# CN-Cape005-via08.net
KiCad netlist of a schematic drawn in EAGLE
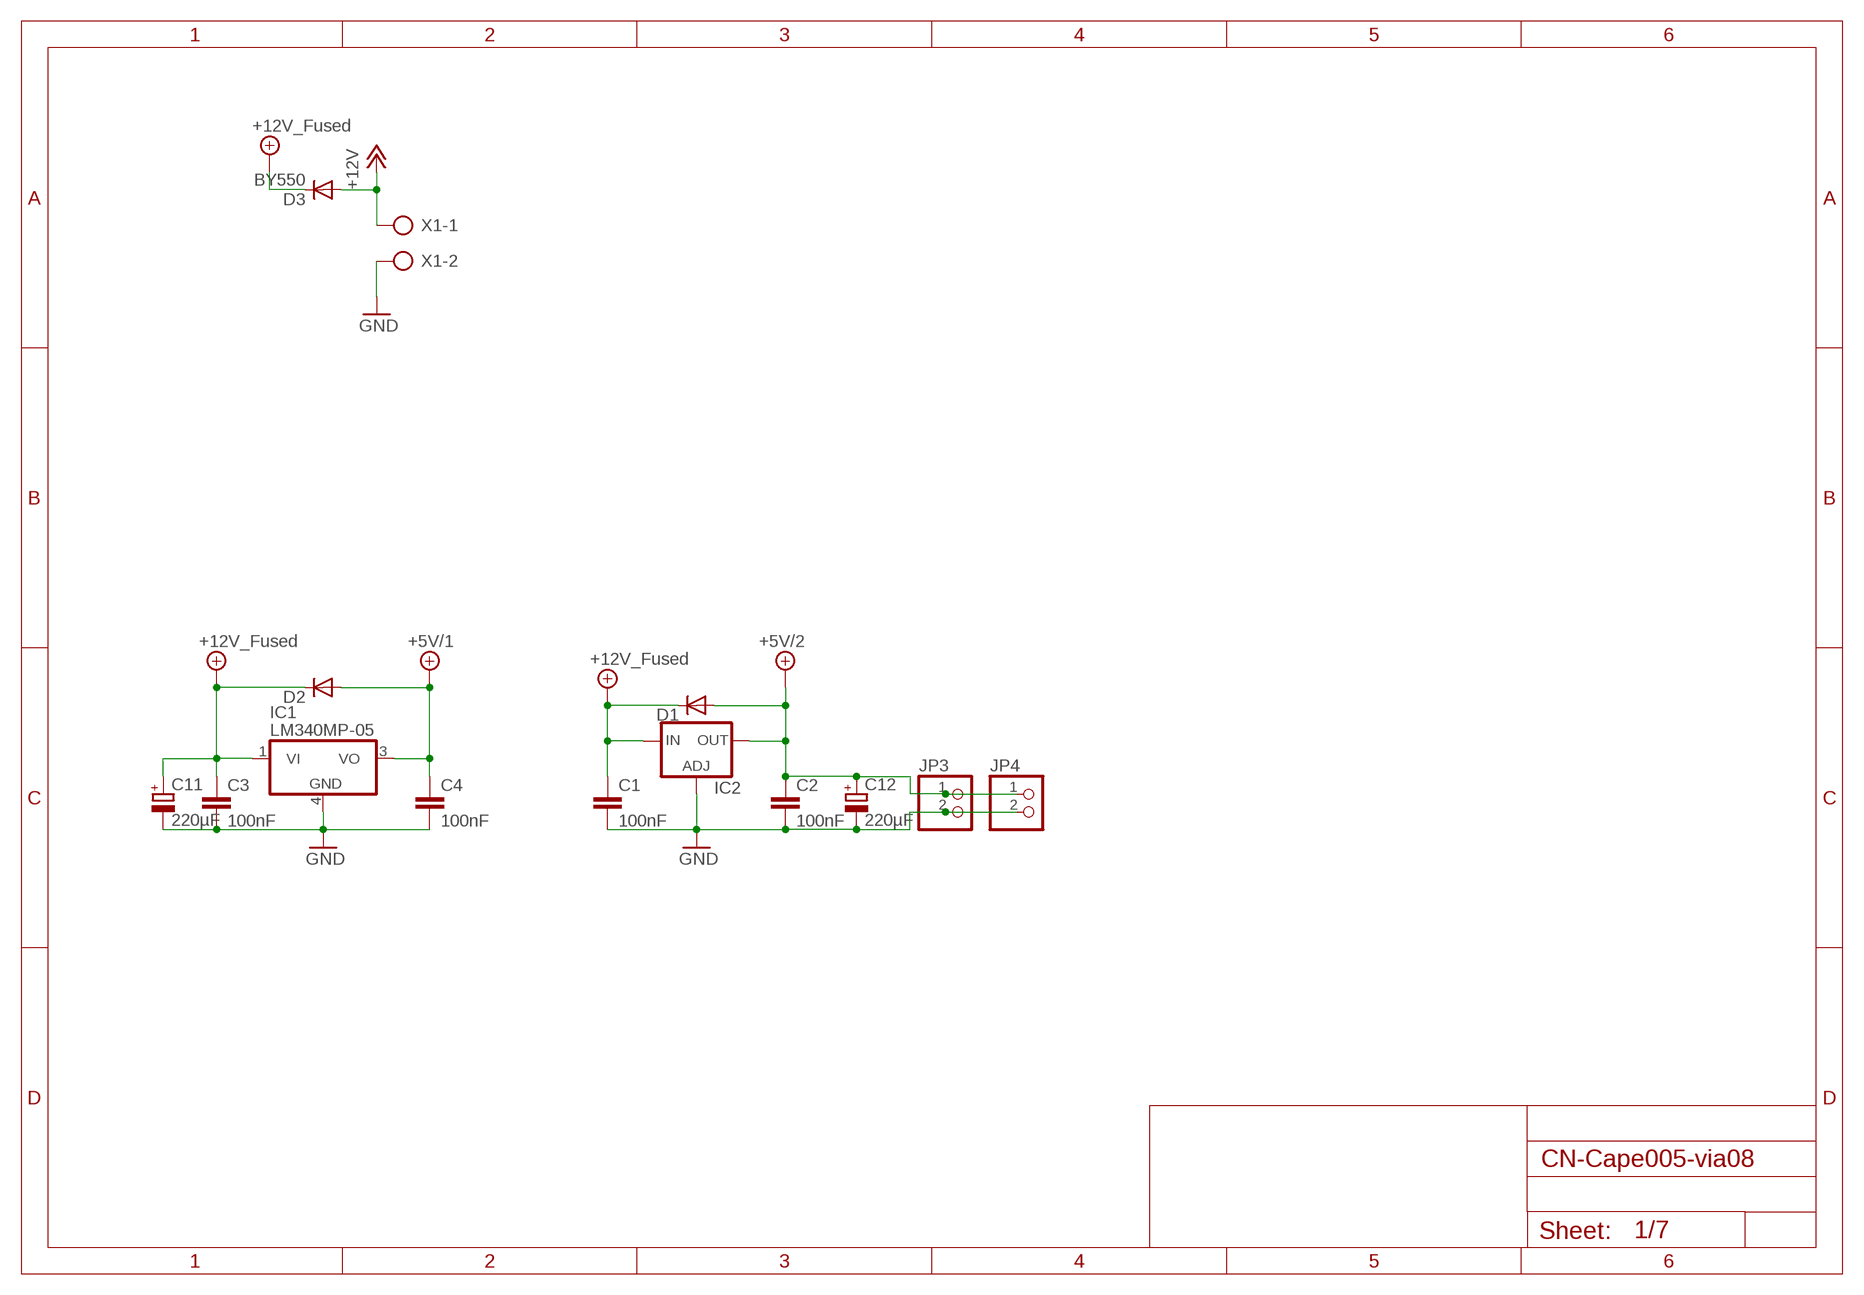
[diagram p0: schematic, sheet 1]
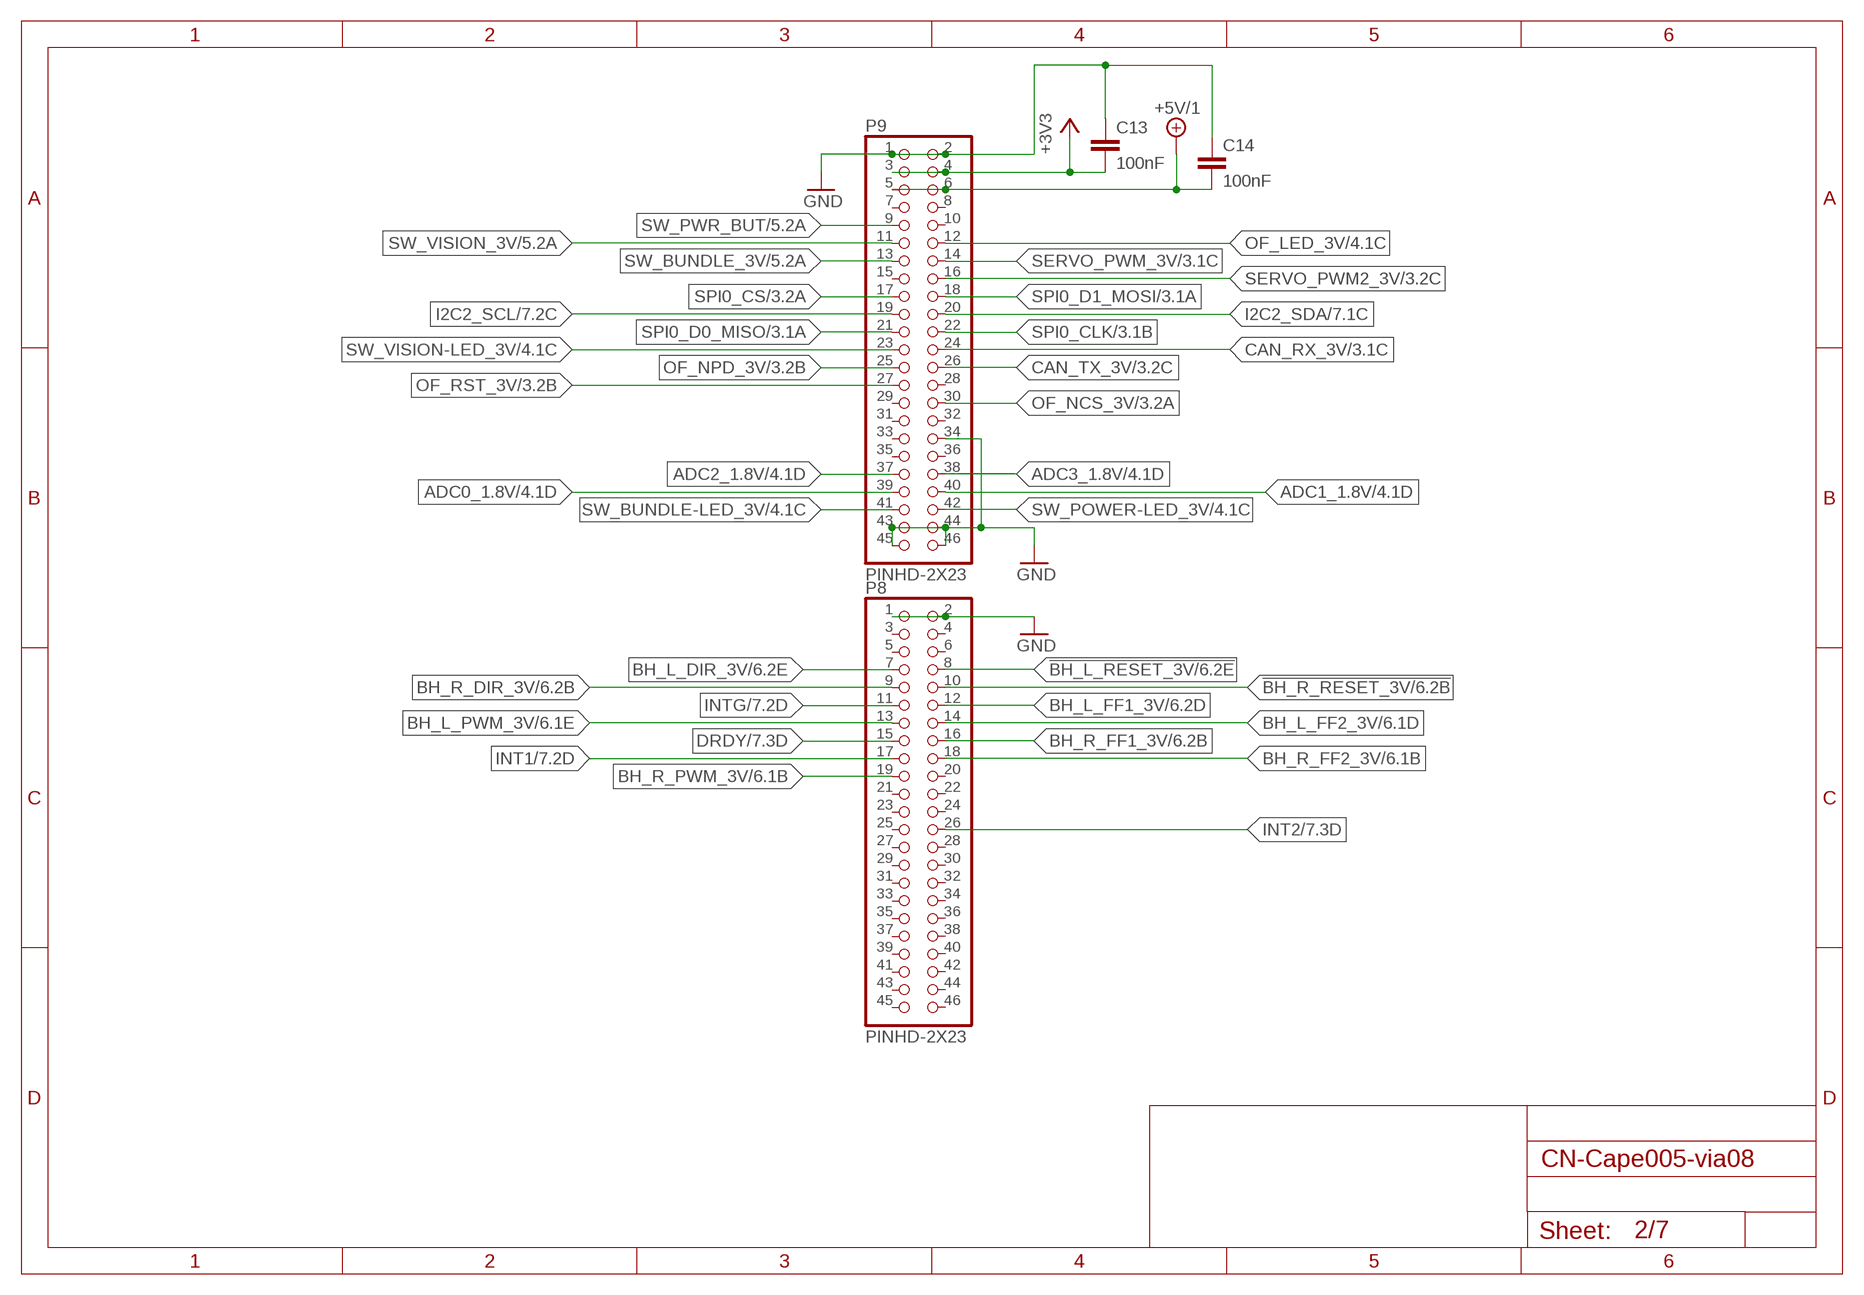
[diagram p1: schematic, sheet 2]
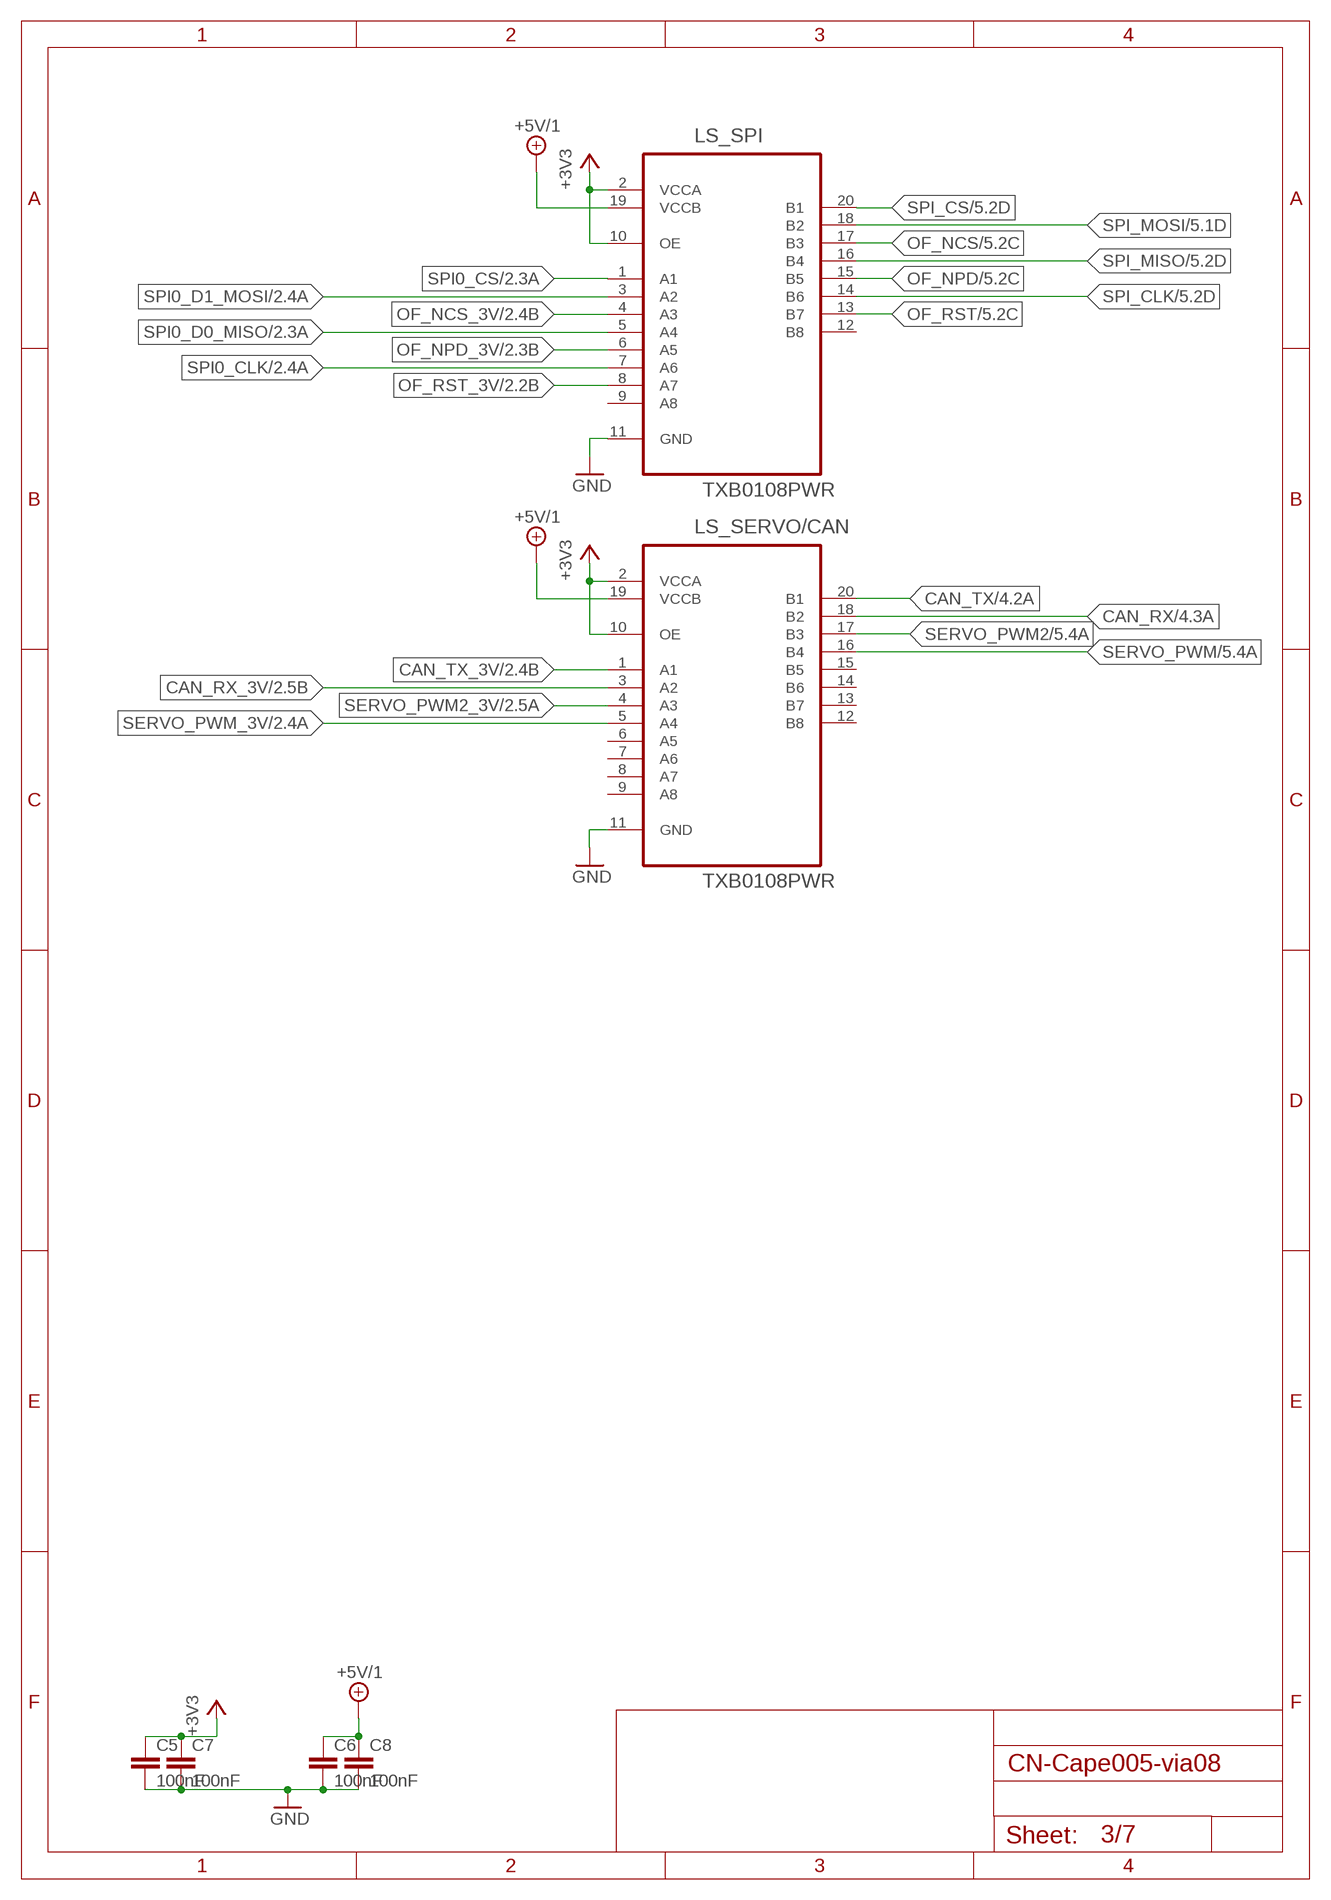
[diagram p2: schematic, sheet 3]
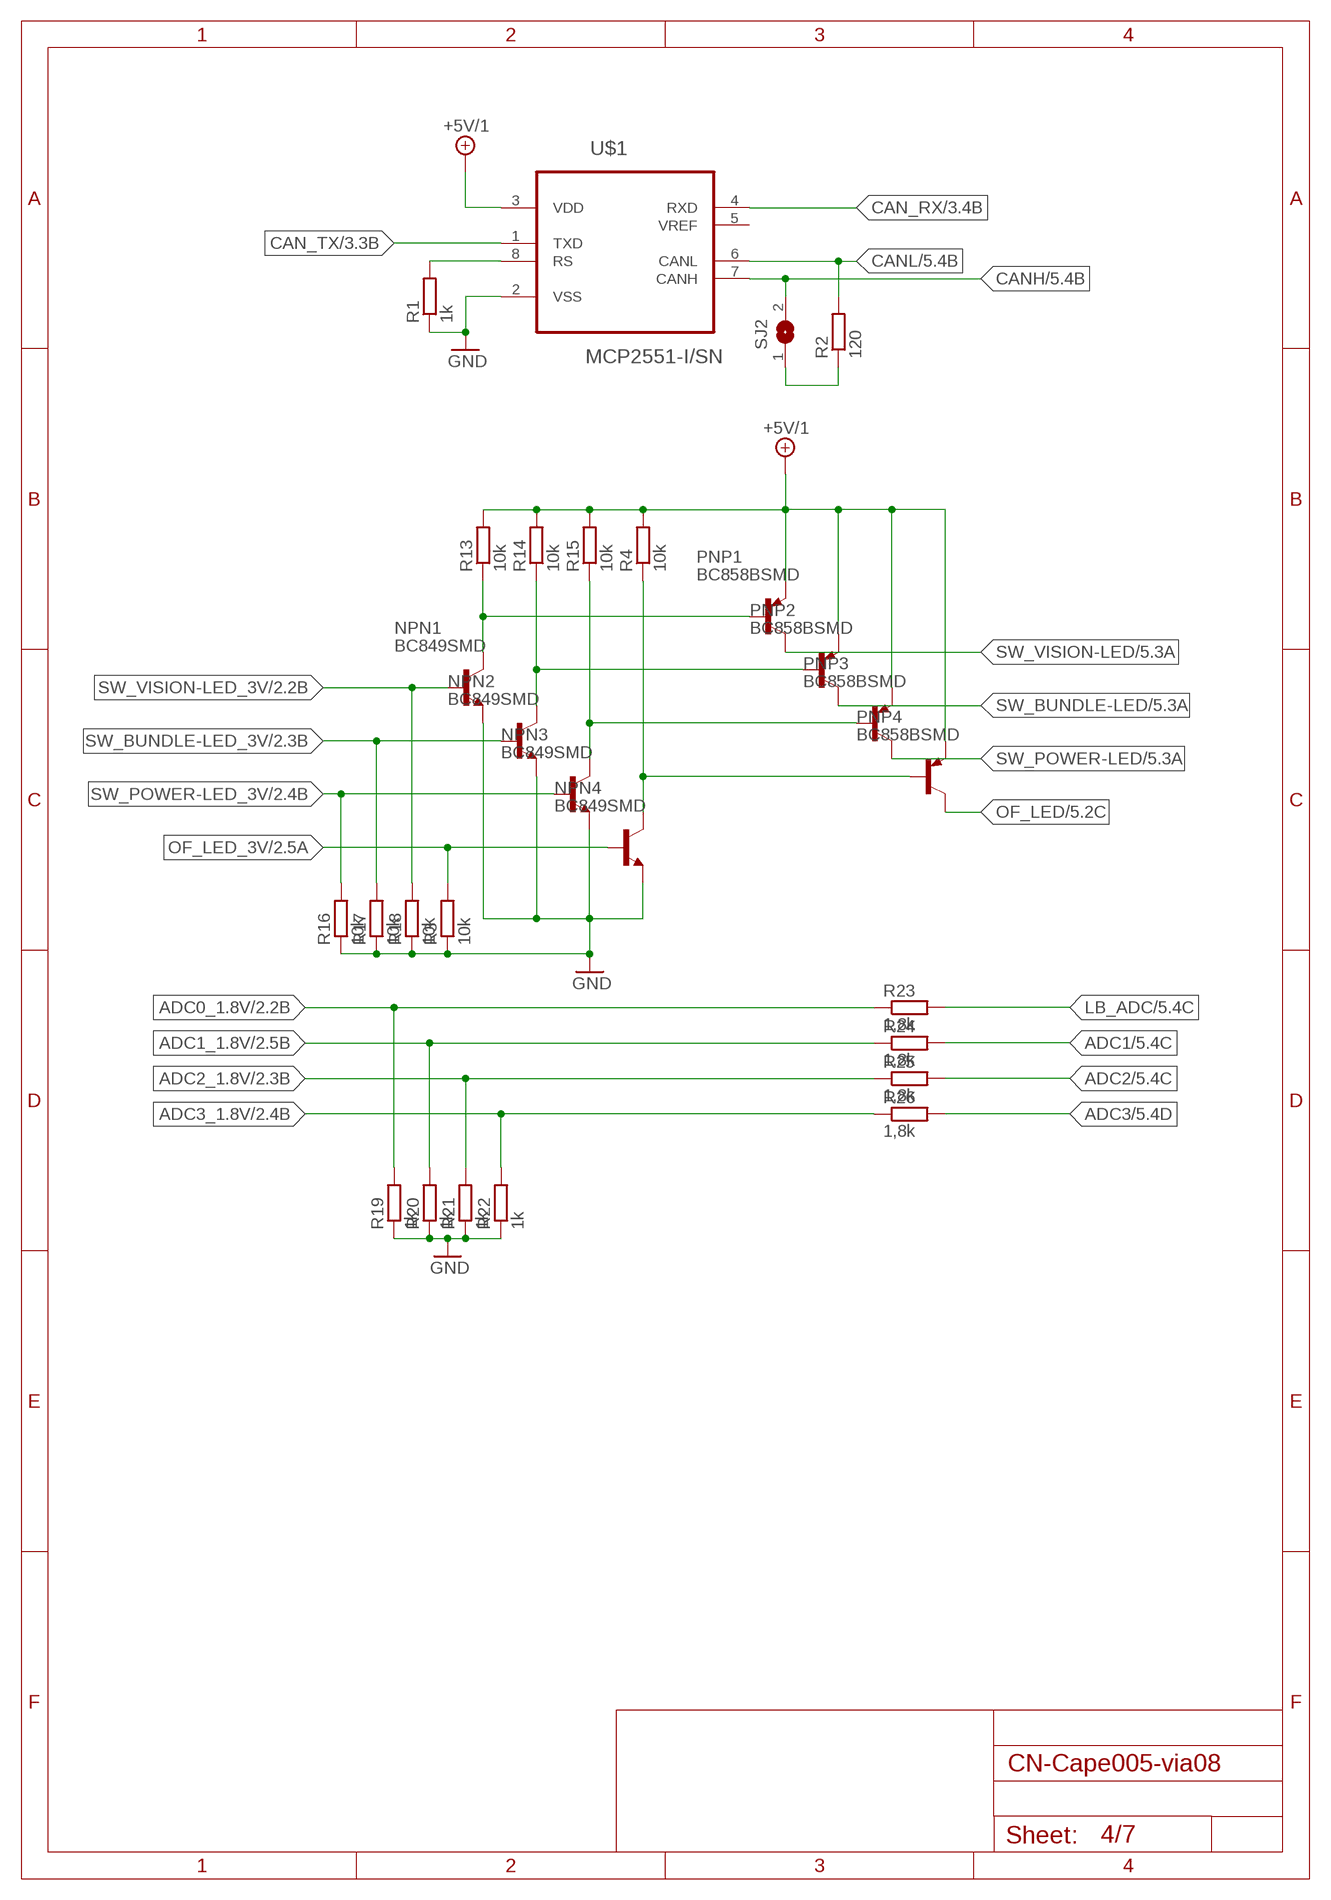
[diagram p3: schematic, sheet 4]
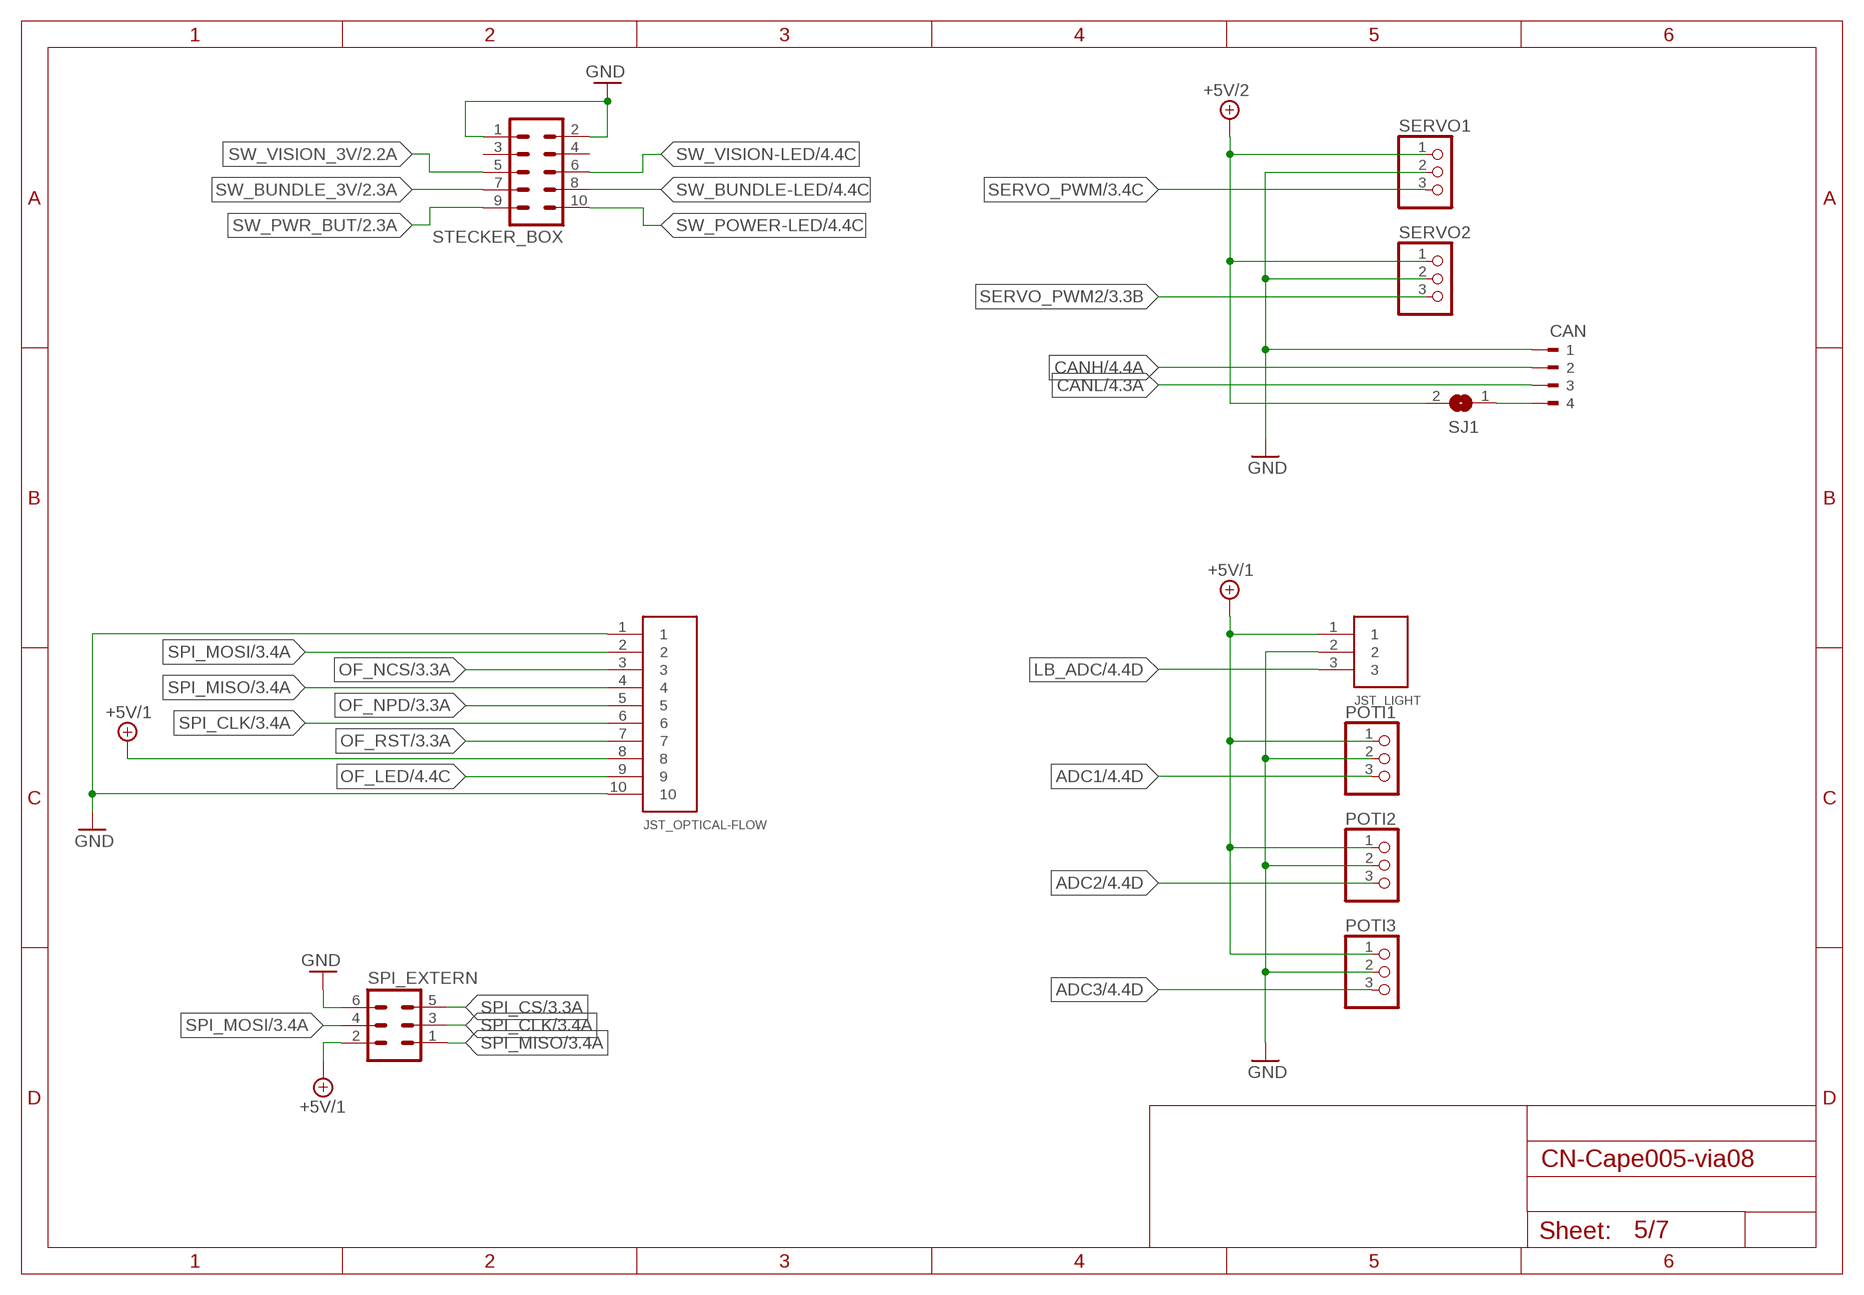
[diagram p4: schematic, sheet 5]
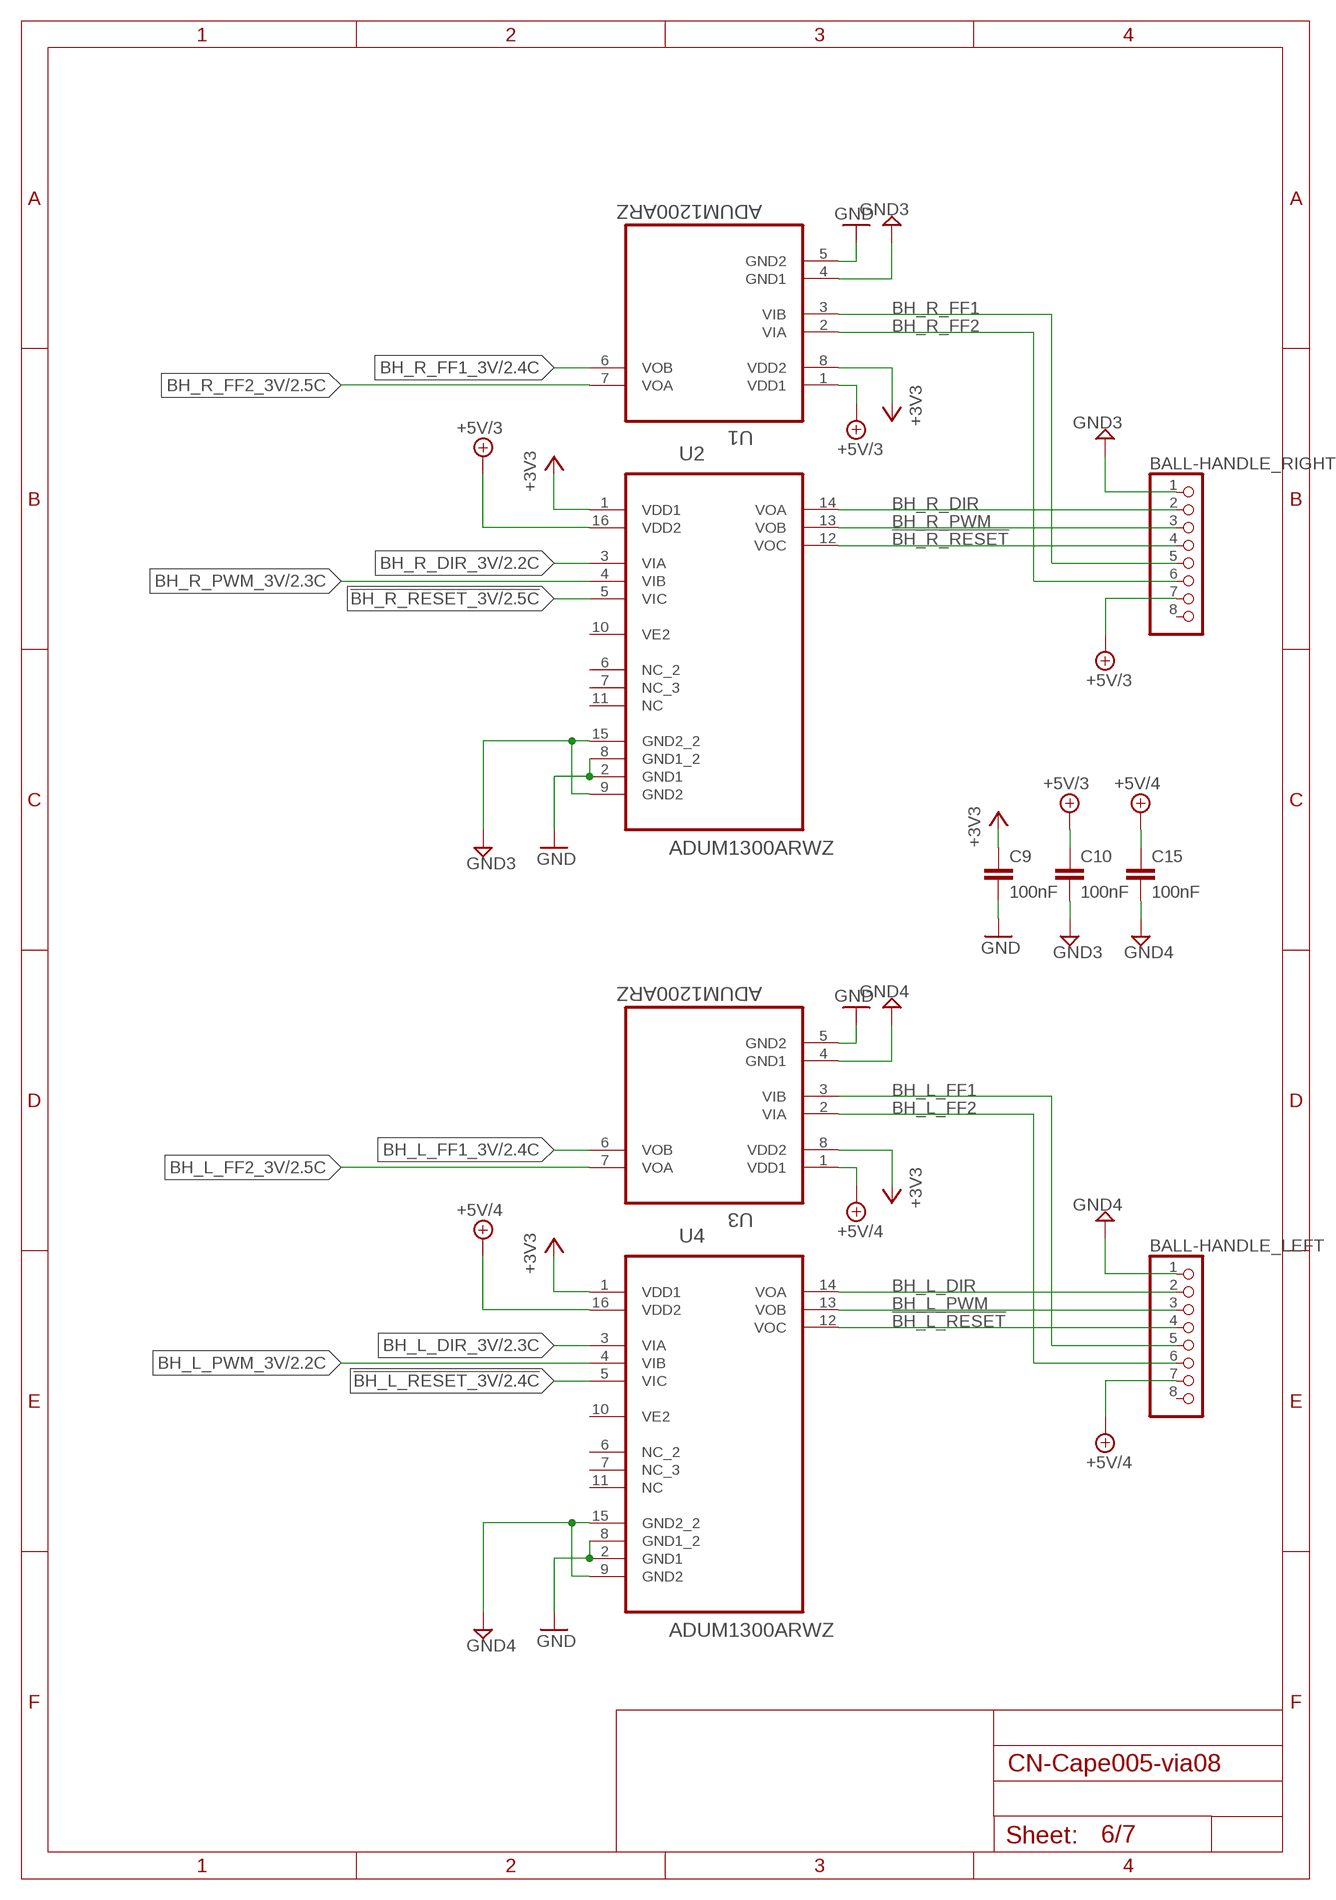
[diagram p5: schematic, sheet 6]
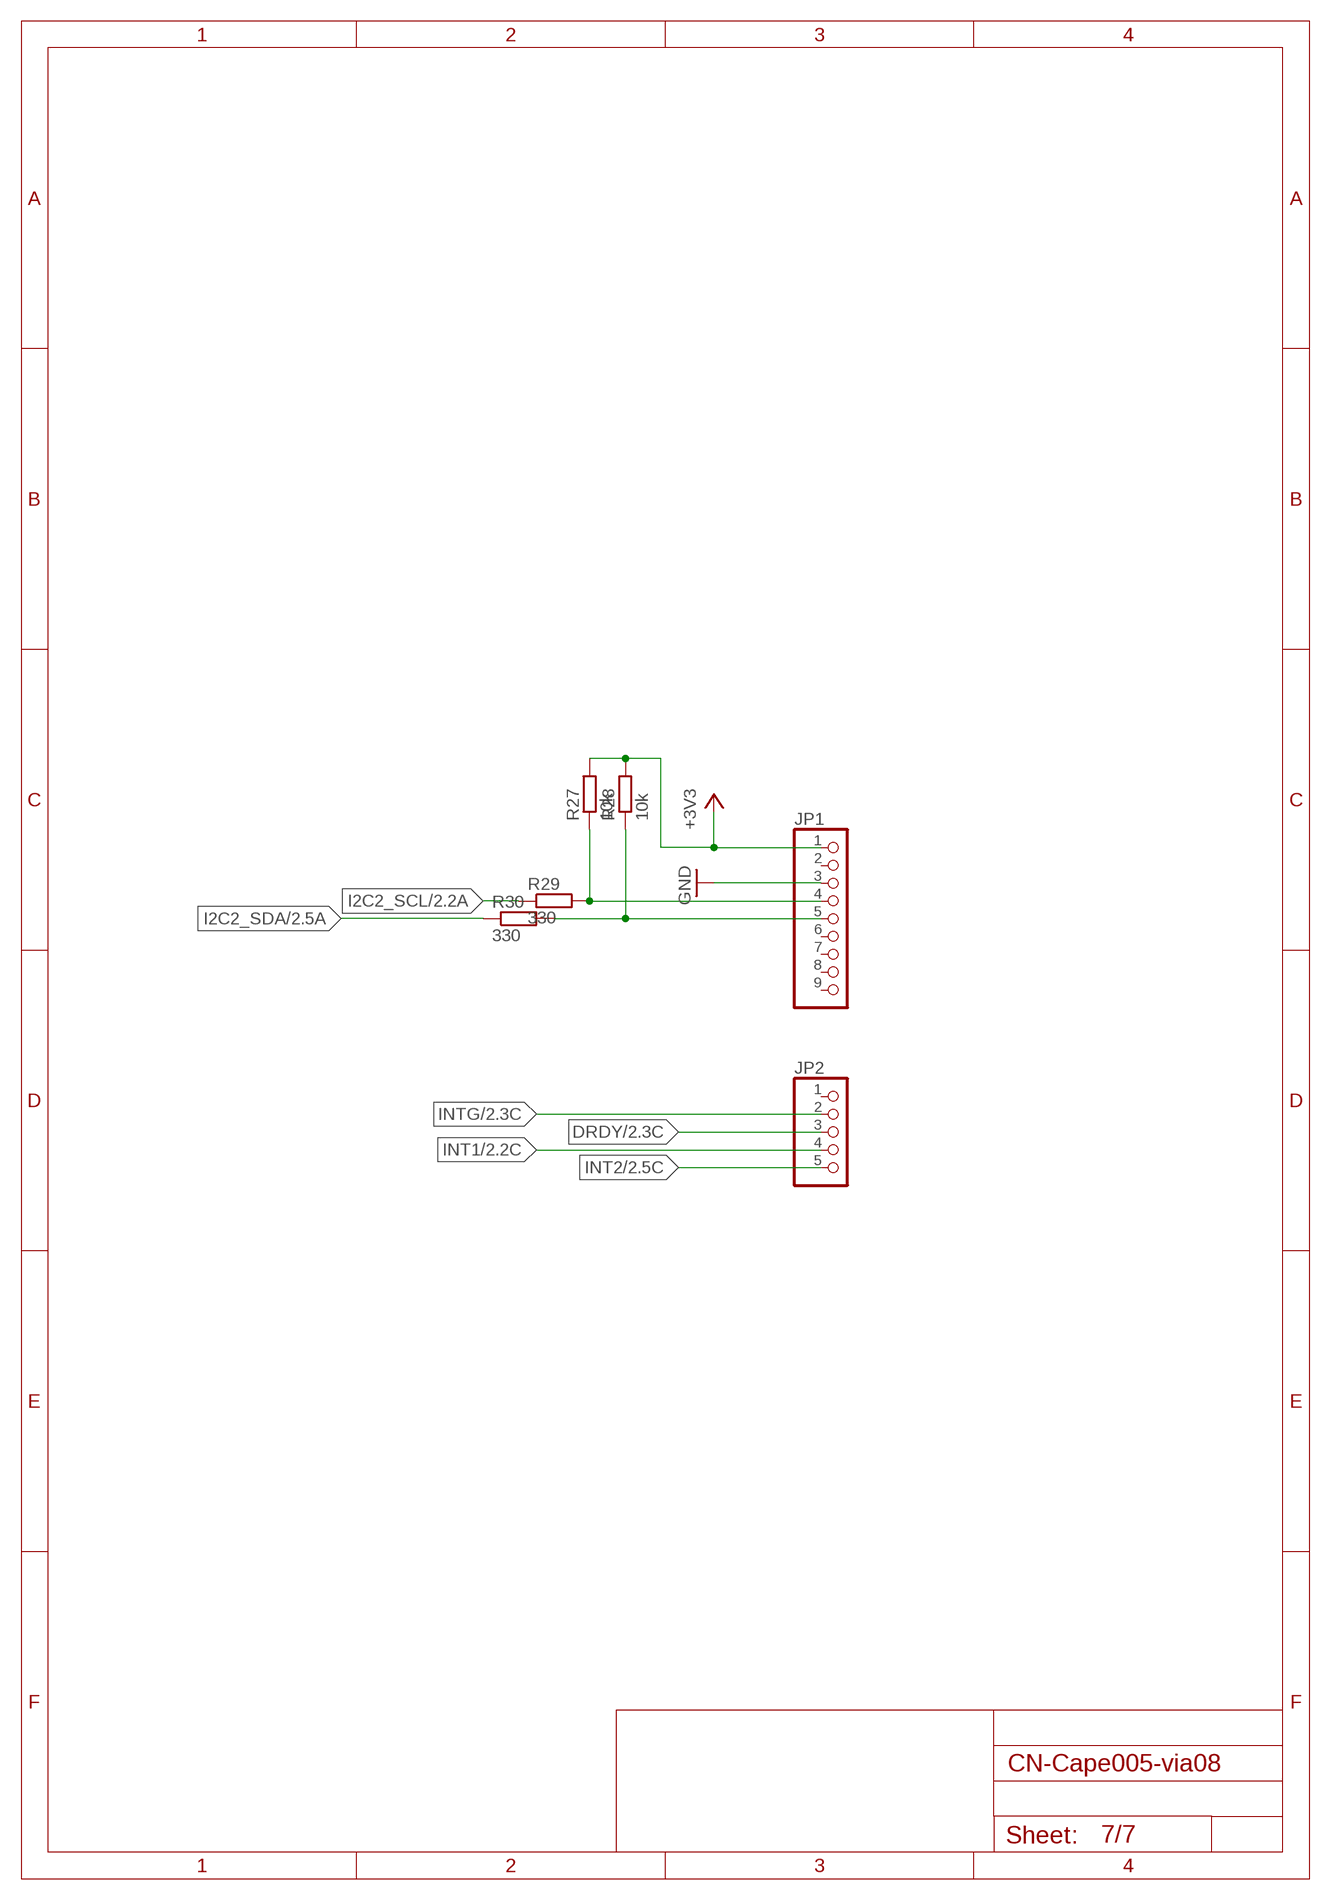
[diagram p6: schematic, sheet 7]

(export (version "E")
  (design (tool "Eeschema 10.0.6"))
  (components
    (comp (ref "C13")
      (value "100nF")
      (footprint "eagle-import:C0603")
      (libsource (lib "eagle-import") (part "C-EUC0603"))
    )
    (comp (ref "C14")
      (value "100nF")
      (footprint "eagle-import:C0603")
      (libsource (lib "eagle-import") (part "C-EUC0603"))
    )
    (comp (ref "P8")
      (value "PINHD-2X23")
      (footprint "eagle-import:2X23")
      (libsource (lib "eagle-import") (part "PINHD-2X23"))
    )
    (comp (ref "P9")
      (value "PINHD-2X23")
      (footprint "eagle-import:2X23")
      (libsource (lib "eagle-import") (part "PINHD-2X23"))
    )
    (comp (ref "C5")
      (value "100nF")
      (footprint "eagle-import:C0603")
      (libsource (lib "eagle-import") (part "C-EUC0603"))
    )
    (comp (ref "C6")
      (value "100nF")
      (footprint "eagle-import:C0603")
      (libsource (lib "eagle-import") (part "C-EUC0603"))
    )
    (comp (ref "C7")
      (value "100nF")
      (footprint "eagle-import:C0603")
      (libsource (lib "eagle-import") (part "C-EUC0603"))
    )
    (comp (ref "C8")
      (value "100nF")
      (footprint "eagle-import:C0603")
      (libsource (lib "eagle-import") (part "C-EUC0603"))
    )
    (comp (ref "LS_SERVO/CAN")
      (value "TXB0108PWR")
      (footprint "eagle-import:SOP65P640X120-20N")
      (libsource (lib "eagle-import") (part "TXB0108PWR"))
    )
    (comp (ref "LS_SPI")
      (value "TXB0108PWR")
      (footprint "eagle-import:SOP65P640X120-20N")
      (libsource (lib "eagle-import") (part "TXB0108PWR"))
    )
    (comp (ref "C1")
      (value "100nF")
      (footprint "eagle-import:C0603")
      (libsource (lib "eagle-import") (part "C-EUC0603"))
    )
    (comp (ref "C2")
      (value "100nF")
      (footprint "eagle-import:C0603")
      (libsource (lib "eagle-import") (part "C-EUC0603"))
    )
    (comp (ref "C3")
      (value "100nF")
      (footprint "eagle-import:C0603")
      (libsource (lib "eagle-import") (part "C-EUC0603"))
    )
    (comp (ref "C4")
      (value "100nF")
      (footprint "eagle-import:C0603")
      (libsource (lib "eagle-import") (part "C-EUC0603"))
    )
    (comp (ref "C11")
      (value "220µF")
      (footprint "eagle-import:E3,5-8")
      (libsource (lib "eagle-import") (part "CPOL-EUE3.5-8"))
    )
    (comp (ref "C12")
      (value "220µF")
      (footprint "eagle-import:E3,5-8")
      (libsource (lib "eagle-import") (part "CPOL-EUE3.5-8"))
    )
    (comp (ref "D1")
      (value "DIODE-SOD123")
      (footprint "eagle-import:SOD123")
      (libsource (lib "eagle-import") (part "DIODE-SOD123"))
    )
    (comp (ref "D2")
      (value "DIODE-SOD123")
      (footprint "eagle-import:SOD123")
      (libsource (lib "eagle-import") (part "DIODE-SOD123"))
    )
    (comp (ref "D3")
      (value "BY550")
      (footprint "eagle-import:DO27-15")
      (libsource (lib "eagle-import") (part "BY550"))
    )
    (comp (ref "IC1")
      (value "LM340MP-05")
      (footprint "eagle-import:SOT223")
      (libsource (lib "eagle-import") (part "LM340?-MP05"))
    )
    (comp (ref "IC2")
      (value "LM138-TL")
      (footprint "eagle-import:TO220L1")
      (libsource (lib "eagle-import") (part "LM138-TL"))
    )
    (comp (ref "JP3")
      (value "PINHD-1X2")
      (footprint "eagle-import:1X02")
      (libsource (lib "eagle-import") (part "PINHD-1X2"))
    )
    (comp (ref "JP4")
      (value "PINHD-1X2")
      (footprint "eagle-import:1X02")
      (libsource (lib "eagle-import") (part "PINHD-1X2"))
    )
    (comp (ref "X1")
      (value "AK500/2-H")
      (footprint "eagle-import:AK500_2-H")
      (libsource (lib "eagle-import") (part "AK500/2-H"))
    )
    (comp (ref "CAN")
      (value "90-4")
      (footprint "eagle-import:90-4")
      (libsource (lib "eagle-import") (part "90-4"))
    )
    (comp (ref "JST_LIGHT")
      (value "S3PIN")
      (footprint "eagle-import:S3B-EH")
      (libsource (lib "eagle-import") (part "S3PIN"))
    )
    (comp (ref "JST_OPTICAL-FLOW")
      (value "S10PIN")
      (footprint "eagle-import:S10B-EH")
      (libsource (lib "eagle-import") (part "S10PIN"))
    )
    (comp (ref "POTI1")
      (value "PINHD-1X3")
      (footprint "eagle-import:1X03")
      (libsource (lib "eagle-import") (part "PINHD-1X3"))
    )
    (comp (ref "POTI2")
      (value "PINHD-1X3")
      (footprint "eagle-import:1X03")
      (libsource (lib "eagle-import") (part "PINHD-1X3"))
    )
    (comp (ref "POTI3")
      (value "PINHD-1X3")
      (footprint "eagle-import:1X03")
      (libsource (lib "eagle-import") (part "PINHD-1X3"))
    )
    (comp (ref "SERVO1")
      (value "PINHD-1X3")
      (footprint "eagle-import:1X03")
      (libsource (lib "eagle-import") (part "PINHD-1X3"))
    )
    (comp (ref "SERVO2")
      (value "PINHD-1X3")
      (footprint "eagle-import:1X03")
      (libsource (lib "eagle-import") (part "PINHD-1X3"))
    )
    (comp (ref "SJ1") (value "SJ") (footprint "eagle-import:SJ") (libsource (lib "eagle-import") (part "SJ")))
    (comp (ref "SPI_EXTERN")
      (value "ML6")
      (footprint "eagle-import:ML6")
      (libsource (lib "eagle-import") (part "ML6"))
    )
    (comp (ref "STECKER_BOX")
      (value "ML10")
      (footprint "eagle-import:ML10")
      (libsource (lib "eagle-import") (part "ML10"))
    )
    (comp (ref "NPN1")
      (value "BC849SMD")
      (footprint "eagle-import:SOT23-BEC")
      (libsource (lib "eagle-import") (part "BC849SMD"))
    )
    (comp (ref "NPN2")
      (value "BC849SMD")
      (footprint "eagle-import:SOT23-BEC")
      (libsource (lib "eagle-import") (part "BC849SMD"))
    )
    (comp (ref "NPN3")
      (value "BC849SMD")
      (footprint "eagle-import:SOT23-BEC")
      (libsource (lib "eagle-import") (part "BC849SMD"))
    )
    (comp (ref "NPN4")
      (value "BC849SMD")
      (footprint "eagle-import:SOT23-BEC")
      (libsource (lib "eagle-import") (part "BC849SMD"))
    )
    (comp (ref "PNP1")
      (value "BC858BSMD")
      (footprint "eagle-import:SOT23-BEC")
      (libsource (lib "eagle-import") (part "BC858SMDB"))
    )
    (comp (ref "PNP2")
      (value "BC858BSMD")
      (footprint "eagle-import:SOT23-BEC")
      (libsource (lib "eagle-import") (part "BC858SMDB"))
    )
    (comp (ref "PNP3")
      (value "BC858BSMD")
      (footprint "eagle-import:SOT23-BEC")
      (libsource (lib "eagle-import") (part "BC858SMDB"))
    )
    (comp (ref "PNP4")
      (value "BC858BSMD")
      (footprint "eagle-import:SOT23-BEC")
      (libsource (lib "eagle-import") (part "BC858SMDB"))
    )
    (comp (ref "R1")
      (value "1k")
      (footprint "eagle-import:R0805")
      (libsource (lib "eagle-import") (part "R-EU_R0805"))
    )
    (comp (ref "R2")
      (value "120")
      (footprint "eagle-import:R0805")
      (libsource (lib "eagle-import") (part "R-EU_R0805"))
    )
    (comp (ref "R3")
      (value "10k")
      (footprint "eagle-import:R0805")
      (libsource (lib "eagle-import") (part "R-EU_R0805"))
    )
    (comp (ref "R4")
      (value "10k")
      (footprint "eagle-import:R0805")
      (libsource (lib "eagle-import") (part "R-EU_R0805"))
    )
    (comp (ref "R13")
      (value "10k")
      (footprint "eagle-import:R0805")
      (libsource (lib "eagle-import") (part "R-EU_R0805"))
    )
    (comp (ref "R14")
      (value "10k")
      (footprint "eagle-import:R0805")
      (libsource (lib "eagle-import") (part "R-EU_R0805"))
    )
    (comp (ref "R15")
      (value "10k")
      (footprint "eagle-import:R0805")
      (libsource (lib "eagle-import") (part "R-EU_R0805"))
    )
    (comp (ref "R16")
      (value "10k")
      (footprint "eagle-import:R0805")
      (libsource (lib "eagle-import") (part "R-EU_R0805"))
    )
    (comp (ref "R17")
      (value "10k")
      (footprint "eagle-import:R0805")
      (libsource (lib "eagle-import") (part "R-EU_R0805"))
    )
    (comp (ref "R18")
      (value "10k")
      (footprint "eagle-import:R0805")
      (libsource (lib "eagle-import") (part "R-EU_R0805"))
    )
    (comp (ref "R19")
      (value "1k")
      (footprint "eagle-import:R0805")
      (libsource (lib "eagle-import") (part "R-EU_R0805"))
    )
    (comp (ref "R20")
      (value "1k")
      (footprint "eagle-import:R0805")
      (libsource (lib "eagle-import") (part "R-EU_R0805"))
    )
    (comp (ref "R21")
      (value "1k")
      (footprint "eagle-import:R0805")
      (libsource (lib "eagle-import") (part "R-EU_R0805"))
    )
    (comp (ref "R22")
      (value "1k")
      (footprint "eagle-import:R0805")
      (libsource (lib "eagle-import") (part "R-EU_R0805"))
    )
    (comp (ref "R23")
      (value "1,8k")
      (footprint "eagle-import:R0805")
      (libsource (lib "eagle-import") (part "R-EU_R0805"))
    )
    (comp (ref "R24")
      (value "1,8k")
      (footprint "eagle-import:R0805")
      (libsource (lib "eagle-import") (part "R-EU_R0805"))
    )
    (comp (ref "R25")
      (value "1,8k")
      (footprint "eagle-import:R0805")
      (libsource (lib "eagle-import") (part "R-EU_R0805"))
    )
    (comp (ref "R26")
      (value "1,8k")
      (footprint "eagle-import:R0805")
      (libsource (lib "eagle-import") (part "R-EU_R0805"))
    )
    (comp (ref "SJ2") (value "SJ") (footprint "eagle-import:SJ") (libsource (lib "eagle-import") (part "SJ")))
    (comp (ref "U$1")
      (value "MCP2551-I/SN")
      (footprint "eagle-import:SOIC127P600X175-8N")
      (libsource (lib "eagle-import") (part "MCP2551-I/SN"))
    )
    (comp (ref "BALL-HANDLE_LEFT")
      (value "PINHD-1X8")
      (footprint "eagle-import:1X08")
      (libsource (lib "eagle-import") (part "PINHD-1X8"))
    )
    (comp (ref "BALL-HANDLE_RIGHT")
      (value "PINHD-1X8")
      (footprint "eagle-import:1X08")
      (libsource (lib "eagle-import") (part "PINHD-1X8"))
    )
    (comp (ref "C9")
      (value "100nF")
      (footprint "eagle-import:C0603")
      (libsource (lib "eagle-import") (part "C-EUC0603"))
    )
    (comp (ref "C10")
      (value "100nF")
      (footprint "eagle-import:C0603")
      (libsource (lib "eagle-import") (part "C-EUC0603"))
    )
    (comp (ref "C15")
      (value "100nF")
      (footprint "eagle-import:C0603")
      (libsource (lib "eagle-import") (part "C-EUC0603"))
    )
    (comp (ref "U1")
      (value "ADUM1200ARZ")
      (footprint "eagle-import:SOIC127P600X175-8N")
      (libsource (lib "eagle-import") (part "ADUM1200ARZ"))
    )
    (comp (ref "U2")
      (value "ADUM1300ARWZ")
      (footprint "eagle-import:SOIC127P1032X265-16N")
      (libsource (lib "eagle-import") (part "ADUM1300ARWZ"))
    )
    (comp (ref "U3")
      (value "ADUM1200ARZ")
      (footprint "eagle-import:SOIC127P600X175-8N")
      (libsource (lib "eagle-import") (part "ADUM1200ARZ"))
    )
    (comp (ref "U4")
      (value "ADUM1300ARWZ")
      (footprint "eagle-import:SOIC127P1032X265-16N")
      (libsource (lib "eagle-import") (part "ADUM1300ARWZ"))
    )
    (comp (ref "JP1")
      (value "PINHD-1X9")
      (footprint "eagle-import:1X09")
      (libsource (lib "eagle-import") (part "PINHD-1X9"))
    )
    (comp (ref "JP2")
      (value "PINHD-1X5")
      (footprint "eagle-import:1X05")
      (libsource (lib "eagle-import") (part "PINHD-1X5"))
    )
    (comp (ref "R27")
      (value "10k")
      (footprint "eagle-import:R0805")
      (libsource (lib "eagle-import") (part "R-EU_R0805"))
    )
    (comp (ref "R28")
      (value "10k")
      (footprint "eagle-import:R0805")
      (libsource (lib "eagle-import") (part "R-EU_R0805"))
    )
    (comp (ref "R29")
      (value "330")
      (footprint "eagle-import:R0805")
      (libsource (lib "eagle-import") (part "R-EU_R0805"))
    )
    (comp (ref "R30")
      (value "330")
      (footprint "eagle-import:R0805")
      (libsource (lib "eagle-import") (part "R-EU_R0805"))
    )
  )
  (nets
    (net (code "1") (name "+3V3") (class "Default")
      (node (ref "C13") (pin "2") (pinfunction "2_2") (pintype "passive"))
      (node (ref "C5") (pin "1") (pinfunction "1_1") (pintype "passive"))
      (node (ref "C7") (pin "1") (pinfunction "1_1") (pintype "passive"))
      (node (ref "C9") (pin "1") (pinfunction "1_1") (pintype "passive"))
      (node (ref "JP1") (pin "1") (pinfunction "1_1") (pintype "passive"))
      (node (ref "LS_SERVO/CAN") (pin "10") (pinfunction "OE_10") (pintype "input"))
      (node (ref "LS_SERVO/CAN") (pin "2") (pinfunction "VCCA_2") (pintype "power_in"))
      (node (ref "LS_SPI") (pin "10") (pinfunction "OE_10") (pintype "input"))
      (node (ref "LS_SPI") (pin "2") (pinfunction "VCCA_2") (pintype "power_in"))
      (node (ref "P9") (pin "3") (pinfunction "3_3") (pintype "passive"))
      (node (ref "P9") (pin "4") (pinfunction "4_4") (pintype "passive"))
      (node (ref "R27") (pin "2") (pinfunction "2_2") (pintype "passive"))
      (node (ref "R28") (pin "2") (pinfunction "2_2") (pintype "passive"))
      (node (ref "U1") (pin "8") (pinfunction "VDD2_8") (pintype "power_in"))
      (node (ref "U2") (pin "1") (pinfunction "VDD1_1") (pintype "power_in"))
      (node (ref "U3") (pin "8") (pinfunction "VDD2_8") (pintype "power_in"))
      (node (ref "U4") (pin "1") (pinfunction "VDD1_1") (pintype "power_in"))
    )
    (net (code "2") (name "+5V{slash}1") (class "Default")
      (node (ref "C14") (pin "2") (pinfunction "2_2") (pintype "passive"))
      (node (ref "C4") (pin "1") (pinfunction "1_1") (pintype "passive"))
      (node (ref "C6") (pin "1") (pinfunction "1_1") (pintype "passive"))
      (node (ref "C8") (pin "1") (pinfunction "1_1") (pintype "passive"))
      (node (ref "D2") (pin "A") (pinfunction "A_A") (pintype "passive"))
      (node (ref "IC1") (pin "3") (pinfunction "VO_3") (pintype "passive"))
      (node (ref "JST_LIGHT") (pin "1") (pinfunction "1_1") (pintype "bidirectional"))
      (node (ref "JST_OPTICAL-FLOW") (pin "8") (pinfunction "8_8") (pintype "bidirectional"))
      (node (ref "LS_SERVO/CAN") (pin "19") (pinfunction "VCCB_19") (pintype "power_in"))
      (node (ref "LS_SPI") (pin "19") (pinfunction "VCCB_19") (pintype "power_in"))
      (node (ref "P9") (pin "5") (pinfunction "5_5") (pintype "passive"))
      (node (ref "P9") (pin "6") (pinfunction "6_6") (pintype "passive"))
      (node (ref "PNP1") (pin "E") (pinfunction "E_E") (pintype "passive"))
      (node (ref "PNP2") (pin "E") (pinfunction "E_E") (pintype "passive"))
      (node (ref "PNP3") (pin "E") (pinfunction "E_E") (pintype "passive"))
      (node (ref "PNP4") (pin "E") (pinfunction "E_E") (pintype "passive"))
      (node (ref "POTI1") (pin "1") (pinfunction "1_1") (pintype "passive"))
      (node (ref "POTI2") (pin "1") (pinfunction "1_1") (pintype "passive"))
      (node (ref "POTI3") (pin "1") (pinfunction "1_1") (pintype "passive"))
      (node (ref "R13") (pin "2") (pinfunction "2_2") (pintype "passive"))
      (node (ref "R14") (pin "2") (pinfunction "2_2") (pintype "passive"))
      (node (ref "R15") (pin "2") (pinfunction "2_2") (pintype "passive"))
      (node (ref "R4") (pin "2") (pinfunction "2_2") (pintype "passive"))
      (node (ref "SPI_EXTERN") (pin "2") (pinfunction "2_2") (pintype "passive"))
      (node (ref "U$1") (pin "3") (pinfunction "VDD_3") (pintype "power_in"))
    )
    (net (code "3") (name "+5V{slash}2") (class "Default")
      (node (ref "C12") (pin "+") (pinfunction "+_+") (pintype "passive"))
      (node (ref "C2") (pin "1") (pinfunction "1_1") (pintype "passive"))
      (node (ref "D1") (pin "A") (pinfunction "A_A") (pintype "passive"))
      (node (ref "IC2") (pin "2") (pinfunction "OUT_2") (pintype "passive"))
      (node (ref "JP3") (pin "1") (pinfunction "1_1") (pintype "passive"))
      (node (ref "JP4") (pin "1") (pinfunction "1_1") (pintype "passive"))
      (node (ref "SERVO1") (pin "1") (pinfunction "1_1") (pintype "passive"))
      (node (ref "SERVO2") (pin "1") (pinfunction "1_1") (pintype "passive"))
      (node (ref "SJ1") (pin "2") (pinfunction "2_2") (pintype "passive"))
    )
    (net (code "4") (name "+5V{slash}3") (class "Default")
      (node (ref "BALL-HANDLE_RIGHT") (pin "7") (pinfunction "7_7") (pintype "passive"))
      (node (ref "C10") (pin "1") (pinfunction "1_1") (pintype "passive"))
      (node (ref "U1") (pin "1") (pinfunction "VDD1_1") (pintype "power_in"))
      (node (ref "U2") (pin "16") (pinfunction "VDD2_16") (pintype "power_in"))
    )
    (net (code "5") (name "+5V{slash}4") (class "Default")
      (node (ref "BALL-HANDLE_LEFT") (pin "7") (pinfunction "7_7") (pintype "passive"))
      (node (ref "C15") (pin "1") (pinfunction "1_1") (pintype "passive"))
      (node (ref "U3") (pin "1") (pinfunction "VDD1_1") (pintype "power_in"))
      (node (ref "U4") (pin "16") (pinfunction "VDD2_16") (pintype "power_in"))
    )
    (net (code "6") (name "+10V") (class "Default")
      (node (ref "C1") (pin "1") (pinfunction "1_1") (pintype "passive"))
      (node (ref "C11") (pin "+") (pinfunction "+_+") (pintype "passive"))
      (node (ref "C3") (pin "1") (pinfunction "1_1") (pintype "passive"))
      (node (ref "D1") (pin "C") (pinfunction "C_C") (pintype "passive"))
      (node (ref "D2") (pin "C") (pinfunction "C_C") (pintype "passive"))
      (node (ref "D3") (pin "C") (pinfunction "C_C") (pintype "passive"))
      (node (ref "IC1") (pin "1") (pinfunction "VI_1") (pintype "input"))
      (node (ref "IC2") (pin "3") (pinfunction "IN_3") (pintype "input"))
    )
    (net (code "7") (name "+12V") (class "Default")
      (node (ref "D3") (pin "A") (pinfunction "A_A") (pintype "passive"))
      (node (ref "X1") (pin "1") (pinfunction "KL_1") (pintype "passive"))
    )
    (net (code "8") (name "ADC0_1.8V") (class "Default")
      (node (ref "P9") (pin "39") (pinfunction "39_39") (pintype "passive"))
      (node (ref "R19") (pin "2") (pinfunction "2_2") (pintype "passive"))
      (node (ref "R23") (pin "1") (pinfunction "1_1") (pintype "passive"))
    )
    (net (code "9") (name "ADC1") (class "Default")
      (node (ref "POTI1") (pin "3") (pinfunction "3_3") (pintype "passive"))
      (node (ref "R24") (pin "2") (pinfunction "2_2") (pintype "passive"))
    )
    (net (code "10") (name "ADC1_1.8V") (class "Default")
      (node (ref "P9") (pin "40") (pinfunction "40_40") (pintype "passive"))
      (node (ref "R20") (pin "2") (pinfunction "2_2") (pintype "passive"))
      (node (ref "R24") (pin "1") (pinfunction "1_1") (pintype "passive"))
    )
    (net (code "11") (name "ADC2") (class "Default")
      (node (ref "POTI2") (pin "3") (pinfunction "3_3") (pintype "passive"))
      (node (ref "R25") (pin "2") (pinfunction "2_2") (pintype "passive"))
    )
    (net (code "12") (name "ADC2_1.8V") (class "Default")
      (node (ref "P9") (pin "37") (pinfunction "37_37") (pintype "passive"))
      (node (ref "R21") (pin "2") (pinfunction "2_2") (pintype "passive"))
      (node (ref "R25") (pin "1") (pinfunction "1_1") (pintype "passive"))
    )
    (net (code "13") (name "ADC3") (class "Default")
      (node (ref "POTI3") (pin "3") (pinfunction "3_3") (pintype "passive"))
      (node (ref "R26") (pin "2") (pinfunction "2_2") (pintype "passive"))
    )
    (net (code "14") (name "ADC3_1.8V") (class "Default")
      (node (ref "P9") (pin "38") (pinfunction "38_38") (pintype "passive"))
      (node (ref "R22") (pin "2") (pinfunction "2_2") (pintype "passive"))
      (node (ref "R26") (pin "1") (pinfunction "1_1") (pintype "passive"))
    )
    (net (code "15") (name "BH_L_DIR") (class "Default")
      (node (ref "BALL-HANDLE_LEFT") (pin "2") (pinfunction "2_2") (pintype "passive"))
      (node (ref "U4") (pin "14") (pinfunction "VOA_14") (pintype "output"))
    )
    (net (code "16") (name "BH_L_DIR_3V") (class "Default")
      (node (ref "P8") (pin "7") (pinfunction "7_7") (pintype "passive"))
      (node (ref "U4") (pin "3") (pinfunction "VIA_3") (pintype "input"))
    )
    (net (code "17") (name "BH_L_FF1") (class "Default")
      (node (ref "BALL-HANDLE_LEFT") (pin "5") (pinfunction "5_5") (pintype "passive"))
      (node (ref "U3") (pin "3") (pinfunction "VIB_3") (pintype "input"))
    )
    (net (code "18") (name "BH_L_FF1_3V") (class "Default")
      (node (ref "P8") (pin "12") (pinfunction "12_12") (pintype "passive"))
      (node (ref "U3") (pin "6") (pinfunction "VOB_6") (pintype "output"))
    )
    (net (code "19") (name "BH_L_FF2") (class "Default")
      (node (ref "BALL-HANDLE_LEFT") (pin "6") (pinfunction "6_6") (pintype "passive"))
      (node (ref "U3") (pin "2") (pinfunction "VIA_2") (pintype "input"))
    )
    (net (code "20") (name "BH_L_FF2_3V") (class "Default")
      (node (ref "P8") (pin "14") (pinfunction "14_14") (pintype "passive"))
      (node (ref "U3") (pin "7") (pinfunction "VOA_7") (pintype "output"))
    )
    (net (code "21") (name "BH_L_PWM") (class "Default")
      (node (ref "BALL-HANDLE_LEFT") (pin "3") (pinfunction "3_3") (pintype "passive"))
      (node (ref "U4") (pin "13") (pinfunction "VOB_13") (pintype "output"))
    )
    (net (code "22") (name "BH_L_PWM_3V") (class "Default")
      (node (ref "P8") (pin "13") (pinfunction "13_13") (pintype "passive"))
      (node (ref "U4") (pin "4") (pinfunction "VIB_4") (pintype "input"))
    )
    (net (code "23") (name "BH_R_DIR") (class "Default")
      (node (ref "BALL-HANDLE_RIGHT") (pin "2") (pinfunction "2_2") (pintype "passive"))
      (node (ref "U2") (pin "14") (pinfunction "VOA_14") (pintype "output"))
    )
    (net (code "24") (name "BH_R_DIR_3V") (class "Default")
      (node (ref "P8") (pin "9") (pinfunction "9_9") (pintype "passive"))
      (node (ref "U2") (pin "3") (pinfunction "VIA_3") (pintype "input"))
    )
    (net (code "25") (name "BH_R_FF1") (class "Default")
      (node (ref "BALL-HANDLE_RIGHT") (pin "5") (pinfunction "5_5") (pintype "passive"))
      (node (ref "U1") (pin "3") (pinfunction "VIB_3") (pintype "input"))
    )
    (net (code "26") (name "BH_R_FF1_3V") (class "Default")
      (node (ref "P8") (pin "16") (pinfunction "16_16") (pintype "passive"))
      (node (ref "U1") (pin "6") (pinfunction "VOB_6") (pintype "output"))
    )
    (net (code "27") (name "BH_R_FF2") (class "Default")
      (node (ref "BALL-HANDLE_RIGHT") (pin "6") (pinfunction "6_6") (pintype "passive"))
      (node (ref "U1") (pin "2") (pinfunction "VIA_2") (pintype "input"))
    )
    (net (code "28") (name "BH_R_FF2_3V") (class "Default")
      (node (ref "P8") (pin "18") (pinfunction "18_18") (pintype "passive"))
      (node (ref "U1") (pin "7") (pinfunction "VOA_7") (pintype "output"))
    )
    (net (code "29") (name "BH_R_PWM") (class "Default")
      (node (ref "BALL-HANDLE_RIGHT") (pin "3") (pinfunction "3_3") (pintype "passive"))
      (node (ref "U2") (pin "13") (pinfunction "VOB_13") (pintype "output"))
    )
    (net (code "30") (name "BH_R_PWM_3V") (class "Default")
      (node (ref "P8") (pin "19") (pinfunction "19_19") (pintype "passive"))
      (node (ref "U2") (pin "4") (pinfunction "VIB_4") (pintype "input"))
    )
    (net (code "31") (name "CANH") (class "Default")
      (node (ref "CAN") (pin "2") (pinfunction "2_2") (pintype "passive"))
      (node (ref "SJ2") (pin "2") (pinfunction "2_2") (pintype "passive"))
      (node (ref "U$1") (pin "7") (pinfunction "CANH_7") (pintype "bidirectional"))
    )
    (net (code "32") (name "CANL") (class "Default")
      (node (ref "CAN") (pin "3") (pinfunction "3_3") (pintype "passive"))
      (node (ref "R2") (pin "2") (pinfunction "2_2") (pintype "passive"))
      (node (ref "U$1") (pin "6") (pinfunction "CANL_6") (pintype "bidirectional"))
    )
    (net (code "33") (name "CAN_RX") (class "Default")
      (node (ref "LS_SERVO/CAN") (pin "18") (pinfunction "B2_18") (pintype "bidirectional"))
      (node (ref "U$1") (pin "4") (pinfunction "RXD_4") (pintype "output"))
    )
    (net (code "34") (name "CAN_RX_3V") (class "Default")
      (node (ref "LS_SERVO/CAN") (pin "3") (pinfunction "A2_3") (pintype "bidirectional"))
      (node (ref "P9") (pin "24") (pinfunction "24_24") (pintype "passive"))
    )
    (net (code "35") (name "CAN_TX") (class "Default")
      (node (ref "LS_SERVO/CAN") (pin "20") (pinfunction "B1_20") (pintype "bidirectional"))
      (node (ref "U$1") (pin "1") (pinfunction "TXD_1") (pintype "input"))
    )
    (net (code "36") (name "CAN_TX_3V") (class "Default")
      (node (ref "LS_SERVO/CAN") (pin "1") (pinfunction "A1_1") (pintype "bidirectional"))
      (node (ref "P9") (pin "26") (pinfunction "26_26") (pintype "passive"))
    )
    (net (code "37") (name "DRDY") (class "Default")
      (node (ref "JP2") (pin "3") (pinfunction "3_3") (pintype "passive"))
      (node (ref "P8") (pin "15") (pinfunction "15_15") (pintype "passive"))
    )
    (net (code "38") (name "GND") (class "Default")
      (node (ref "C1") (pin "2") (pinfunction "2_2") (pintype "passive"))
      (node (ref "C11") (pin "-") (pinfunction "-_-") (pintype "passive"))
      (node (ref "C12") (pin "-") (pinfunction "-_-") (pintype "passive"))
      (node (ref "C13") (pin "1") (pinfunction "1_1") (pintype "passive"))
      (node (ref "C14") (pin "1") (pinfunction "1_1") (pintype "passive"))
      (node (ref "C2") (pin "2") (pinfunction "2_2") (pintype "passive"))
      (node (ref "C3") (pin "2") (pinfunction "2_2") (pintype "passive"))
      (node (ref "C4") (pin "2") (pinfunction "2_2") (pintype "passive"))
      (node (ref "C5") (pin "2") (pinfunction "2_2") (pintype "passive"))
      (node (ref "C6") (pin "2") (pinfunction "2_2") (pintype "passive"))
      (node (ref "C7") (pin "2") (pinfunction "2_2") (pintype "passive"))
      (node (ref "C8") (pin "2") (pinfunction "2_2") (pintype "passive"))
      (node (ref "C9") (pin "2") (pinfunction "2_2") (pintype "passive"))
      (node (ref "CAN") (pin "1") (pinfunction "1_1") (pintype "passive"))
      (node (ref "IC1") (pin "4") (pinfunction "GND_4") (pintype "passive"))
      (node (ref "IC2") (pin "1") (pinfunction "ADJ_1") (pintype "input"))
      (node (ref "JP1") (pin "3") (pinfunction "3_3") (pintype "passive"))
      (node (ref "JP3") (pin "2") (pinfunction "2_2") (pintype "passive"))
      (node (ref "JP4") (pin "2") (pinfunction "2_2") (pintype "passive"))
      (node (ref "JST_LIGHT") (pin "2") (pinfunction "2_2") (pintype "bidirectional"))
      (node (ref "JST_OPTICAL-FLOW") (pin "1") (pinfunction "1_1") (pintype "bidirectional"))
      (node (ref "JST_OPTICAL-FLOW") (pin "10") (pinfunction "10_10") (pintype "bidirectional"))
      (node (ref "LS_SERVO/CAN") (pin "11") (pinfunction "GND_11") (pintype "passive"))
      (node (ref "LS_SPI") (pin "11") (pinfunction "GND_11") (pintype "passive"))
      (node (ref "NPN1") (pin "E") (pinfunction "E_E") (pintype "passive"))
      (node (ref "NPN2") (pin "E") (pinfunction "E_E") (pintype "passive"))
      (node (ref "NPN3") (pin "E") (pinfunction "E_E") (pintype "passive"))
      (node (ref "NPN4") (pin "E") (pinfunction "E_E") (pintype "passive"))
      (node (ref "P8") (pin "1") (pinfunction "1_1") (pintype "passive"))
      (node (ref "P8") (pin "2") (pinfunction "2_2") (pintype "passive"))
      (node (ref "P9") (pin "1") (pinfunction "1_1") (pintype "passive"))
      (node (ref "P9") (pin "2") (pinfunction "2_2") (pintype "passive"))
      (node (ref "P9") (pin "34") (pinfunction "34_34") (pintype "passive"))
      (node (ref "P9") (pin "43") (pinfunction "43_43") (pintype "passive"))
      (node (ref "P9") (pin "44") (pinfunction "44_44") (pintype "passive"))
      (node (ref "P9") (pin "45") (pinfunction "45_45") (pintype "passive"))
      (node (ref "P9") (pin "46") (pinfunction "46_46") (pintype "passive"))
      (node (ref "POTI1") (pin "2") (pinfunction "2_2") (pintype "passive"))
      (node (ref "POTI2") (pin "2") (pinfunction "2_2") (pintype "passive"))
      (node (ref "POTI3") (pin "2") (pinfunction "2_2") (pintype "passive"))
      (node (ref "R1") (pin "1") (pinfunction "1_1") (pintype "passive"))
      (node (ref "R16") (pin "1") (pinfunction "1_1") (pintype "passive"))
      (node (ref "R17") (pin "1") (pinfunction "1_1") (pintype "passive"))
      (node (ref "R18") (pin "1") (pinfunction "1_1") (pintype "passive"))
      (node (ref "R19") (pin "1") (pinfunction "1_1") (pintype "passive"))
      (node (ref "R20") (pin "1") (pinfunction "1_1") (pintype "passive"))
      (node (ref "R21") (pin "1") (pinfunction "1_1") (pintype "passive"))
      (node (ref "R22") (pin "1") (pinfunction "1_1") (pintype "passive"))
      (node (ref "R3") (pin "1") (pinfunction "1_1") (pintype "passive"))
      (node (ref "SERVO1") (pin "2") (pinfunction "2_2") (pintype "passive"))
      (node (ref "SERVO2") (pin "2") (pinfunction "2_2") (pintype "passive"))
      (node (ref "SPI_EXTERN") (pin "6") (pinfunction "6_6") (pintype "passive"))
      (node (ref "STECKER_BOX") (pin "1") (pinfunction "1_1") (pintype "passive"))
      (node (ref "STECKER_BOX") (pin "2") (pinfunction "2_2") (pintype "passive"))
      (node (ref "U$1") (pin "2") (pinfunction "VSS_2") (pintype "passive"))
      (node (ref "U1") (pin "5") (pinfunction "GND2_5") (pintype "passive"))
      (node (ref "U2") (pin "2") (pinfunction "GND1_2") (pintype "passive"))
      (node (ref "U2") (pin "8") (pinfunction "GND1_2_8") (pintype "passive"))
      (node (ref "U3") (pin "5") (pinfunction "GND2_5") (pintype "passive"))
      (node (ref "U4") (pin "2") (pinfunction "GND1_2") (pintype "passive"))
      (node (ref "U4") (pin "8") (pinfunction "GND1_2_8") (pintype "passive"))
      (node (ref "X1") (pin "2") (pinfunction "KL_2") (pintype "passive"))
    )
    (net (code "39") (name "GND3") (class "Default")
      (node (ref "BALL-HANDLE_RIGHT") (pin "1") (pinfunction "1_1") (pintype "passive"))
      (node (ref "C10") (pin "2") (pinfunction "2_2") (pintype "passive"))
      (node (ref "U1") (pin "4") (pinfunction "GND1_4") (pintype "passive"))
      (node (ref "U2") (pin "15") (pinfunction "GND2_2_15") (pintype "passive"))
      (node (ref "U2") (pin "9") (pinfunction "GND2_9") (pintype "passive"))
    )
    (net (code "40") (name "GND4") (class "Default")
      (node (ref "BALL-HANDLE_LEFT") (pin "1") (pinfunction "1_1") (pintype "passive"))
      (node (ref "C15") (pin "2") (pinfunction "2_2") (pintype "passive"))
      (node (ref "U3") (pin "4") (pinfunction "GND1_4") (pintype "passive"))
      (node (ref "U4") (pin "15") (pinfunction "GND2_2_15") (pintype "passive"))
      (node (ref "U4") (pin "9") (pinfunction "GND2_9") (pintype "passive"))
    )
    (net (code "41") (name "I2C2_SCL") (class "Default")
      (node (ref "P9") (pin "19") (pinfunction "19_19") (pintype "passive"))
      (node (ref "R29") (pin "1") (pinfunction "1_1") (pintype "passive"))
    )
    (net (code "42") (name "I2C2_SDA") (class "Default")
      (node (ref "P9") (pin "20") (pinfunction "20_20") (pintype "passive"))
      (node (ref "R30") (pin "1") (pinfunction "1_1") (pintype "passive"))
    )
    (net (code "43") (name "INT1") (class "Default")
      (node (ref "JP2") (pin "4") (pinfunction "4_4") (pintype "passive"))
      (node (ref "P8") (pin "17") (pinfunction "17_17") (pintype "passive"))
    )
    (net (code "44") (name "INT2") (class "Default")
      (node (ref "JP2") (pin "5") (pinfunction "5_5") (pintype "passive"))
      (node (ref "P8") (pin "26") (pinfunction "26_26") (pintype "passive"))
    )
    (net (code "45") (name "INTG") (class "Default")
      (node (ref "JP2") (pin "2") (pinfunction "2_2") (pintype "passive"))
      (node (ref "P8") (pin "11") (pinfunction "11_11") (pintype "passive"))
    )
    (net (code "46") (name "LB_ADC") (class "Default")
      (node (ref "JST_LIGHT") (pin "3") (pinfunction "3_3") (pintype "bidirectional"))
      (node (ref "R23") (pin "2") (pinfunction "2_2") (pintype "passive"))
    )
    (net (code "47") (name "Net-(CAN-Pad4)") (class "Default")
      (node (ref "CAN") (pin "4") (pinfunction "4_4") (pintype "passive"))
      (node (ref "SJ1") (pin "1") (pinfunction "1_1") (pintype "passive"))
    )
    (net (code "48") (name "Net-(JP1-Pad4)") (class "Default")
      (node (ref "JP1") (pin "4") (pinfunction "4_4") (pintype "passive"))
      (node (ref "R27") (pin "1") (pinfunction "1_1") (pintype "passive"))
      (node (ref "R29") (pin "2") (pinfunction "2_2") (pintype "passive"))
    )
    (net (code "49") (name "Net-(JP1-Pad5)") (class "Default")
      (node (ref "JP1") (pin "5") (pinfunction "5_5") (pintype "passive"))
      (node (ref "R28") (pin "1") (pinfunction "1_1") (pintype "passive"))
      (node (ref "R30") (pin "2") (pinfunction "2_2") (pintype "passive"))
    )
    (net (code "50") (name "Net-(NPN1-PadC)") (class "Default")
      (node (ref "NPN1") (pin "C") (pinfunction "C_C") (pintype "passive"))
      (node (ref "PNP1") (pin "B") (pinfunction "B_B") (pintype "passive"))
      (node (ref "R13") (pin "1") (pinfunction "1_1") (pintype "passive"))
    )
    (net (code "51") (name "Net-(NPN2-PadC)") (class "Default")
      (node (ref "NPN2") (pin "C") (pinfunction "C_C") (pintype "passive"))
      (node (ref "PNP2") (pin "B") (pinfunction "B_B") (pintype "passive"))
      (node (ref "R14") (pin "1") (pinfunction "1_1") (pintype "passive"))
    )
    (net (code "52") (name "Net-(NPN3-PadC)") (class "Default")
      (node (ref "NPN3") (pin "C") (pinfunction "C_C") (pintype "passive"))
      (node (ref "PNP3") (pin "B") (pinfunction "B_B") (pintype "passive"))
      (node (ref "R15") (pin "1") (pinfunction "1_1") (pintype "passive"))
    )
    (net (code "53") (name "Net-(NPN4-PadC)") (class "Default")
      (node (ref "NPN4") (pin "C") (pinfunction "C_C") (pintype "passive"))
      (node (ref "PNP4") (pin "B") (pinfunction "B_B") (pintype "passive"))
      (node (ref "R4") (pin "1") (pinfunction "1_1") (pintype "passive"))
    )
    (net (code "54") (name "Net-(R2-Pad1)") (class "Default")
      (node (ref "R2") (pin "1") (pinfunction "1_1") (pintype "passive"))
      (node (ref "SJ2") (pin "1") (pinfunction "1_1") (pintype "passive"))
    )
    (net (code "55") (name "Net-(U$1-RS)") (class "Default")
      (node (ref "R1") (pin "2") (pinfunction "2_2") (pintype "passive"))
      (node (ref "U$1") (pin "8") (pinfunction "RS_8") (pintype "input"))
    )
    (net (code "56") (name "OF_LED") (class "Default")
      (node (ref "JST_OPTICAL-FLOW") (pin "9") (pinfunction "9_9") (pintype "bidirectional"))
      (node (ref "PNP4") (pin "C") (pinfunction "C_C") (pintype "passive"))
    )
    (net (code "57") (name "OF_LED_3V") (class "Default")
      (node (ref "NPN4") (pin "B") (pinfunction "B_B") (pintype "passive"))
      (node (ref "P9") (pin "12") (pinfunction "12_12") (pintype "passive"))
      (node (ref "R3") (pin "2") (pinfunction "2_2") (pintype "passive"))
    )
    (net (code "58") (name "OF_NCS") (class "Default")
      (node (ref "JST_OPTICAL-FLOW") (pin "3") (pinfunction "3_3") (pintype "bidirectional"))
      (node (ref "LS_SPI") (pin "17") (pinfunction "B3_17") (pintype "bidirectional"))
    )
    (net (code "59") (name "OF_NCS_3V") (class "Default")
      (node (ref "LS_SPI") (pin "4") (pinfunction "A3_4") (pintype "bidirectional"))
      (node (ref "P9") (pin "30") (pinfunction "30_30") (pintype "passive"))
    )
    (net (code "60") (name "OF_NPD") (class "Default")
      (node (ref "JST_OPTICAL-FLOW") (pin "5") (pinfunction "5_5") (pintype "bidirectional"))
      (node (ref "LS_SPI") (pin "15") (pinfunction "B5_15") (pintype "bidirectional"))
    )
    (net (code "61") (name "OF_NPD_3V") (class "Default")
      (node (ref "LS_SPI") (pin "6") (pinfunction "A5_6") (pintype "bidirectional"))
      (node (ref "P9") (pin "25") (pinfunction "25_25") (pintype "passive"))
    )
    (net (code "62") (name "OF_RST") (class "Default")
      (node (ref "JST_OPTICAL-FLOW") (pin "7") (pinfunction "7_7") (pintype "bidirectional"))
      (node (ref "LS_SPI") (pin "13") (pinfunction "B7_13") (pintype "bidirectional"))
    )
    (net (code "63") (name "OF_RST_3V") (class "Default")
      (node (ref "LS_SPI") (pin "8") (pinfunction "A7_8") (pintype "bidirectional"))
      (node (ref "P9") (pin "27") (pinfunction "27_27") (pintype "passive"))
    )
    (net (code "64") (name "SERVO_PWM") (class "Default")
      (node (ref "LS_SERVO/CAN") (pin "16") (pinfunction "B4_16") (pintype "bidirectional"))
      (node (ref "SERVO1") (pin "3") (pinfunction "3_3") (pintype "passive"))
    )
    (net (code "65") (name "SERVO_PWM2") (class "Default")
      (node (ref "LS_SERVO/CAN") (pin "17") (pinfunction "B3_17") (pintype "bidirectional"))
      (node (ref "SERVO2") (pin "3") (pinfunction "3_3") (pintype "passive"))
    )
    (net (code "66") (name "SERVO_PWM2_3V") (class "Default")
      (node (ref "LS_SERVO/CAN") (pin "4") (pinfunction "A3_4") (pintype "bidirectional"))
      (node (ref "P9") (pin "16") (pinfunction "16_16") (pintype "passive"))
    )
    (net (code "67") (name "SERVO_PWM_3V") (class "Default")
      (node (ref "LS_SERVO/CAN") (pin "5") (pinfunction "A4_5") (pintype "bidirectional"))
      (node (ref "P9") (pin "14") (pinfunction "14_14") (pintype "passive"))
    )
    (net (code "68") (name "SPI0_CLK") (class "Default")
      (node (ref "LS_SPI") (pin "7") (pinfunction "A6_7") (pintype "bidirectional"))
      (node (ref "P9") (pin "22") (pinfunction "22_22") (pintype "passive"))
    )
    (net (code "69") (name "SPI0_CS") (class "Default")
      (node (ref "LS_SPI") (pin "1") (pinfunction "A1_1") (pintype "bidirectional"))
      (node (ref "P9") (pin "17") (pinfunction "17_17") (pintype "passive"))
    )
    (net (code "70") (name "SPI0_D0_MISO") (class "Default")
      (node (ref "LS_SPI") (pin "5") (pinfunction "A4_5") (pintype "bidirectional"))
      (node (ref "P9") (pin "21") (pinfunction "21_21") (pintype "passive"))
    )
    (net (code "71") (name "SPI0_D1_MOSI") (class "Default")
      (node (ref "LS_SPI") (pin "3") (pinfunction "A2_3") (pintype "bidirectional"))
      (node (ref "P9") (pin "18") (pinfunction "18_18") (pintype "passive"))
    )
    (net (code "72") (name "SPI_CLK") (class "Default")
      (node (ref "JST_OPTICAL-FLOW") (pin "6") (pinfunction "6_6") (pintype "bidirectional"))
      (node (ref "LS_SPI") (pin "14") (pinfunction "B6_14") (pintype "bidirectional"))
      (node (ref "SPI_EXTERN") (pin "3") (pinfunction "3_3") (pintype "passive"))
    )
    (net (code "73") (name "SPI_CS") (class "Default")
      (node (ref "LS_SPI") (pin "20") (pinfunction "B1_20") (pintype "bidirectional"))
      (node (ref "SPI_EXTERN") (pin "5") (pinfunction "5_5") (pintype "passive"))
    )
    (net (code "74") (name "SPI_MISO") (class "Default")
      (node (ref "JST_OPTICAL-FLOW") (pin "4") (pinfunction "4_4") (pintype "bidirectional"))
      (node (ref "LS_SPI") (pin "16") (pinfunction "B4_16") (pintype "bidirectional"))
      (node (ref "SPI_EXTERN") (pin "1") (pinfunction "1_1") (pintype "passive"))
    )
    (net (code "75") (name "SPI_MOSI") (class "Default")
      (node (ref "JST_OPTICAL-FLOW") (pin "2") (pinfunction "2_2") (pintype "bidirectional"))
      (node (ref "LS_SPI") (pin "18") (pinfunction "B2_18") (pintype "bidirectional"))
      (node (ref "SPI_EXTERN") (pin "4") (pinfunction "4_4") (pintype "passive"))
    )
    (net (code "76") (name "SW_BUNDLE-LED") (class "Default")
      (node (ref "PNP2") (pin "C") (pinfunction "C_C") (pintype "passive"))
      (node (ref "STECKER_BOX") (pin "8") (pinfunction "8_8") (pintype "passive"))
    )
    (net (code "77") (name "SW_BUNDLE-LED_3V") (class "Default")
      (node (ref "NPN2") (pin "B") (pinfunction "B_B") (pintype "passive"))
      (node (ref "P9") (pin "41") (pinfunction "41_41") (pintype "passive"))
      (node (ref "R17") (pin "2") (pinfunction "2_2") (pintype "passive"))
    )
    (net (code "78") (name "SW_BUNDLE_3V") (class "Default")
      (node (ref "P9") (pin "13") (pinfunction "13_13") (pintype "passive"))
      (node (ref "STECKER_BOX") (pin "7") (pinfunction "7_7") (pintype "passive"))
    )
    (net (code "79") (name "SW_POWER-LED") (class "Default")
      (node (ref "PNP3") (pin "C") (pinfunction "C_C") (pintype "passive"))
      (node (ref "STECKER_BOX") (pin "10") (pinfunction "10_10") (pintype "passive"))
    )
    (net (code "80") (name "SW_POWER-LED_3V") (class "Default")
      (node (ref "NPN3") (pin "B") (pinfunction "B_B") (pintype "passive"))
      (node (ref "P9") (pin "42") (pinfunction "42_42") (pintype "passive"))
      (node (ref "R16") (pin "2") (pinfunction "2_2") (pintype "passive"))
    )
    (net (code "81") (name "SW_PWR_BUT") (class "Default")
      (node (ref "P9") (pin "9") (pinfunction "9_9") (pintype "passive"))
      (node (ref "STECKER_BOX") (pin "9") (pinfunction "9_9") (pintype "passive"))
    )
    (net (code "82") (name "SW_VISION-LED") (class "Default")
      (node (ref "PNP1") (pin "C") (pinfunction "C_C") (pintype "passive"))
      (node (ref "STECKER_BOX") (pin "6") (pinfunction "6_6") (pintype "passive"))
    )
    (net (code "83") (name "SW_VISION-LED_3V") (class "Default")
      (node (ref "NPN1") (pin "B") (pinfunction "B_B") (pintype "passive"))
      (node (ref "P9") (pin "23") (pinfunction "23_23") (pintype "passive"))
      (node (ref "R18") (pin "2") (pinfunction "2_2") (pintype "passive"))
    )
    (net (code "84") (name "SW_VISION_3V") (class "Default")
      (node (ref "P9") (pin "11") (pinfunction "11_11") (pintype "passive"))
      (node (ref "STECKER_BOX") (pin "5") (pinfunction "5_5") (pintype "passive"))
    )
    (net (code "85") (name "unconnected-(BALL-HANDLE_LEFT-Pad8)") (class "Default")
      (node (ref "BALL-HANDLE_LEFT") (pin "8") (pinfunction "8_8") (pintype "passive"))
    )
    (net (code "86") (name "unconnected-(BALL-HANDLE_RIGHT-Pad8)") (class "Default")
      (node (ref "BALL-HANDLE_RIGHT") (pin "8") (pinfunction "8_8") (pintype "passive"))
    )
    (net (code "87") (name "unconnected-(JP1-Pad2)") (class "Default")
      (node (ref "JP1") (pin "2") (pinfunction "2_2") (pintype "passive"))
    )
    (net (code "88") (name "unconnected-(JP1-Pad6)") (class "Default")
      (node (ref "JP1") (pin "6") (pinfunction "6_6") (pintype "passive"))
    )
    (net (code "89") (name "unconnected-(JP1-Pad7)") (class "Default")
      (node (ref "JP1") (pin "7") (pinfunction "7_7") (pintype "passive"))
    )
    (net (code "90") (name "unconnected-(JP1-Pad8)") (class "Default")
      (node (ref "JP1") (pin "8") (pinfunction "8_8") (pintype "passive"))
    )
    (net (code "91") (name "unconnected-(JP1-Pad9)") (class "Default")
      (node (ref "JP1") (pin "9") (pinfunction "9_9") (pintype "passive"))
    )
    (net (code "92") (name "unconnected-(JP2-Pad1)") (class "Default")
      (node (ref "JP2") (pin "1") (pinfunction "1_1") (pintype "passive"))
    )
    (net (code "93") (name "unconnected-(LS_SERVO/CAN-A5-Pad6)") (class "Default")
      (node (ref "LS_SERVO/CAN") (pin "6") (pinfunction "A5_6") (pintype "bidirectional"))
    )
    (net (code "94") (name "unconnected-(LS_SERVO/CAN-A6-Pad7)") (class "Default")
      (node (ref "LS_SERVO/CAN") (pin "7") (pinfunction "A6_7") (pintype "bidirectional"))
    )
    (net (code "95") (name "unconnected-(LS_SERVO/CAN-A7-Pad8)") (class "Default")
      (node (ref "LS_SERVO/CAN") (pin "8") (pinfunction "A7_8") (pintype "bidirectional"))
    )
    (net (code "96") (name "unconnected-(LS_SERVO/CAN-A8-Pad9)") (class "Default")
      (node (ref "LS_SERVO/CAN") (pin "9") (pinfunction "A8_9") (pintype "bidirectional"))
    )
    (net (code "97") (name "unconnected-(LS_SERVO/CAN-B5-Pad15)") (class "Default")
      (node (ref "LS_SERVO/CAN") (pin "15") (pinfunction "B5_15") (pintype "bidirectional"))
    )
    (net (code "98") (name "unconnected-(LS_SERVO/CAN-B6-Pad14)") (class "Default")
      (node (ref "LS_SERVO/CAN") (pin "14") (pinfunction "B6_14") (pintype "bidirectional"))
    )
    (net (code "99") (name "unconnected-(LS_SERVO/CAN-B7-Pad13)") (class "Default")
      (node (ref "LS_SERVO/CAN") (pin "13") (pinfunction "B7_13") (pintype "bidirectional"))
    )
    (net (code "100") (name "unconnected-(LS_SERVO/CAN-B8-Pad12)") (class "Default")
      (node (ref "LS_SERVO/CAN") (pin "12") (pinfunction "B8_12") (pintype "bidirectional"))
    )
    (net (code "101") (name "unconnected-(LS_SPI-A8-Pad9)") (class "Default")
      (node (ref "LS_SPI") (pin "9") (pinfunction "A8_9") (pintype "bidirectional"))
    )
    (net (code "102") (name "unconnected-(LS_SPI-B8-Pad12)") (class "Default")
      (node (ref "LS_SPI") (pin "12") (pinfunction "B8_12") (pintype "bidirectional"))
    )
    (net (code "103") (name "unconnected-(P8-Pad3)") (class "Default")
      (node (ref "P8") (pin "3") (pinfunction "3_3") (pintype "passive"))
    )
    (net (code "104") (name "unconnected-(P8-Pad4)") (class "Default")
      (node (ref "P8") (pin "4") (pinfunction "4_4") (pintype "passive"))
    )
    (net (code "105") (name "unconnected-(P8-Pad5)") (class "Default")
      (node (ref "P8") (pin "5") (pinfunction "5_5") (pintype "passive"))
    )
    (net (code "106") (name "unconnected-(P8-Pad6)") (class "Default")
      (node (ref "P8") (pin "6") (pinfunction "6_6") (pintype "passive"))
    )
    (net (code "107") (name "unconnected-(P8-Pad20)") (class "Default")
      (node (ref "P8") (pin "20") (pinfunction "20_20") (pintype "passive"))
    )
    (net (code "108") (name "unconnected-(P8-Pad21)") (class "Default")
      (node (ref "P8") (pin "21") (pinfunction "21_21") (pintype "passive"))
    )
    (net (code "109") (name "unconnected-(P8-Pad22)") (class "Default")
      (node (ref "P8") (pin "22") (pinfunction "22_22") (pintype "passive"))
    )
    (net (code "110") (name "unconnected-(P8-Pad23)") (class "Default")
      (node (ref "P8") (pin "23") (pinfunction "23_23") (pintype "passive"))
    )
    (net (code "111") (name "unconnected-(P8-Pad24)") (class "Default")
      (node (ref "P8") (pin "24") (pinfunction "24_24") (pintype "passive"))
    )
    (net (code "112") (name "unconnected-(P8-Pad25)") (class "Default")
      (node (ref "P8") (pin "25") (pinfunction "25_25") (pintype "passive"))
    )
    (net (code "113") (name "unconnected-(P8-Pad27)") (class "Default")
      (node (ref "P8") (pin "27") (pinfunction "27_27") (pintype "passive"))
    )
    (net (code "114") (name "unconnected-(P8-Pad28)") (class "Default")
      (node (ref "P8") (pin "28") (pinfunction "28_28") (pintype "passive"))
    )
    (net (code "115") (name "unconnected-(P8-Pad29)") (class "Default")
      (node (ref "P8") (pin "29") (pinfunction "29_29") (pintype "passive"))
    )
    (net (code "116") (name "unconnected-(P8-Pad30)") (class "Default")
      (node (ref "P8") (pin "30") (pinfunction "30_30") (pintype "passive"))
    )
    (net (code "117") (name "unconnected-(P8-Pad31)") (class "Default")
      (node (ref "P8") (pin "31") (pinfunction "31_31") (pintype "passive"))
    )
    (net (code "118") (name "unconnected-(P8-Pad32)") (class "Default")
      (node (ref "P8") (pin "32") (pinfunction "32_32") (pintype "passive"))
    )
    (net (code "119") (name "unconnected-(P8-Pad33)") (class "Default")
      (node (ref "P8") (pin "33") (pinfunction "33_33") (pintype "passive"))
    )
    (net (code "120") (name "unconnected-(P8-Pad34)") (class "Default")
      (node (ref "P8") (pin "34") (pinfunction "34_34") (pintype "passive"))
    )
    (net (code "121") (name "unconnected-(P8-Pad35)") (class "Default")
      (node (ref "P8") (pin "35") (pinfunction "35_35") (pintype "passive"))
    )
    (net (code "122") (name "unconnected-(P8-Pad36)") (class "Default")
      (node (ref "P8") (pin "36") (pinfunction "36_36") (pintype "passive"))
    )
    (net (code "123") (name "unconnected-(P8-Pad37)") (class "Default")
      (node (ref "P8") (pin "37") (pinfunction "37_37") (pintype "passive"))
    )
    (net (code "124") (name "unconnected-(P8-Pad38)") (class "Default")
      (node (ref "P8") (pin "38") (pinfunction "38_38") (pintype "passive"))
    )
    (net (code "125") (name "unconnected-(P8-Pad39)") (class "Default")
      (node (ref "P8") (pin "39") (pinfunction "39_39") (pintype "passive"))
    )
    (net (code "126") (name "unconnected-(P8-Pad40)") (class "Default")
      (node (ref "P8") (pin "40") (pinfunction "40_40") (pintype "passive"))
    )
    (net (code "127") (name "unconnected-(P8-Pad41)") (class "Default")
      (node (ref "P8") (pin "41") (pinfunction "41_41") (pintype "passive"))
    )
    (net (code "128") (name "unconnected-(P8-Pad42)") (class "Default")
      (node (ref "P8") (pin "42") (pinfunction "42_42") (pintype "passive"))
    )
    (net (code "129") (name "unconnected-(P8-Pad43)") (class "Default")
      (node (ref "P8") (pin "43") (pinfunction "43_43") (pintype "passive"))
    )
    (net (code "130") (name "unconnected-(P8-Pad44)") (class "Default")
      (node (ref "P8") (pin "44") (pinfunction "44_44") (pintype "passive"))
    )
    (net (code "131") (name "unconnected-(P8-Pad45)") (class "Default")
      (node (ref "P8") (pin "45") (pinfunction "45_45") (pintype "passive"))
    )
    (net (code "132") (name "unconnected-(P8-Pad46)") (class "Default")
      (node (ref "P8") (pin "46") (pinfunction "46_46") (pintype "passive"))
    )
    (net (code "133") (name "unconnected-(P9-Pad7)") (class "Default")
      (node (ref "P9") (pin "7") (pinfunction "7_7") (pintype "passive"))
    )
    (net (code "134") (name "unconnected-(P9-Pad8)") (class "Default")
      (node (ref "P9") (pin "8") (pinfunction "8_8") (pintype "passive"))
    )
    (net (code "135") (name "unconnected-(P9-Pad10)") (class "Default")
      (node (ref "P9") (pin "10") (pinfunction "10_10") (pintype "passive"))
    )
    (net (code "136") (name "unconnected-(P9-Pad15)") (class "Default")
      (node (ref "P9") (pin "15") (pinfunction "15_15") (pintype "passive"))
    )
    (net (code "137") (name "unconnected-(P9-Pad28)") (class "Default")
      (node (ref "P9") (pin "28") (pinfunction "28_28") (pintype "passive"))
    )
    (net (code "138") (name "unconnected-(P9-Pad29)") (class "Default")
      (node (ref "P9") (pin "29") (pinfunction "29_29") (pintype "passive"))
    )
    (net (code "139") (name "unconnected-(P9-Pad31)") (class "Default")
      (node (ref "P9") (pin "31") (pinfunction "31_31") (pintype "passive"))
    )
    (net (code "140") (name "unconnected-(P9-Pad32)") (class "Default")
      (node (ref "P9") (pin "32") (pinfunction "32_32") (pintype "passive"))
    )
    (net (code "141") (name "unconnected-(P9-Pad33)") (class "Default")
      (node (ref "P9") (pin "33") (pinfunction "33_33") (pintype "passive"))
    )
    (net (code "142") (name "unconnected-(P9-Pad35)") (class "Default")
      (node (ref "P9") (pin "35") (pinfunction "35_35") (pintype "passive"))
    )
    (net (code "143") (name "unconnected-(P9-Pad36)") (class "Default")
      (node (ref "P9") (pin "36") (pinfunction "36_36") (pintype "passive"))
    )
    (net (code "144") (name "unconnected-(STECKER_BOX-Pad3)") (class "Default")
      (node (ref "STECKER_BOX") (pin "3") (pinfunction "3_3") (pintype "passive"))
    )
    (net (code "145") (name "unconnected-(STECKER_BOX-Pad4)") (class "Default")
      (node (ref "STECKER_BOX") (pin "4") (pinfunction "4_4") (pintype "passive"))
    )
    (net (code "146") (name "unconnected-(U$1-VREF-Pad5)") (class "Default")
      (node (ref "U$1") (pin "5") (pinfunction "VREF_5") (pintype "output"))
    )
    (net (code "147") (name "unconnected-(U2-NC-Pad11)") (class "Default")
      (node (ref "U2") (pin "11") (pinfunction "NC_11") (pintype "no_connect"))
    )
    (net (code "148") (name "unconnected-(U2-NC_2-Pad6)") (class "Default")
      (node (ref "U2") (pin "6") (pinfunction "NC_2_6") (pintype "no_connect"))
    )
    (net (code "149") (name "unconnected-(U2-NC_3-Pad7)") (class "Default")
      (node (ref "U2") (pin "7") (pinfunction "NC_3_7") (pintype "no_connect"))
    )
    (net (code "150") (name "unconnected-(U2-VE2-Pad10)") (class "Default")
      (node (ref "U2") (pin "10") (pinfunction "VE2_10") (pintype "input"))
    )
    (net (code "151") (name "unconnected-(U4-NC-Pad11)") (class "Default")
      (node (ref "U4") (pin "11") (pinfunction "NC_11") (pintype "no_connect"))
    )
    (net (code "152") (name "unconnected-(U4-NC_2-Pad6)") (class "Default")
      (node (ref "U4") (pin "6") (pinfunction "NC_2_6") (pintype "no_connect"))
    )
    (net (code "153") (name "unconnected-(U4-NC_3-Pad7)") (class "Default")
      (node (ref "U4") (pin "7") (pinfunction "NC_3_7") (pintype "no_connect"))
    )
    (net (code "154") (name "unconnected-(U4-VE2-Pad10)") (class "Default")
      (node (ref "U4") (pin "10") (pinfunction "VE2_10") (pintype "input"))
    )
    (net (code "155") (name "~{BH_L_RESET_3V}") (class "Default")
      (node (ref "P8") (pin "8") (pinfunction "8_8") (pintype "passive"))
      (node (ref "U4") (pin "5") (pinfunction "VIC_5") (pintype "input"))
    )
    (net (code "156") (name "~{BH_L_RESET}") (class "Default")
      (node (ref "BALL-HANDLE_LEFT") (pin "4") (pinfunction "4_4") (pintype "passive"))
      (node (ref "U4") (pin "12") (pinfunction "VOC_12") (pintype "output"))
    )
    (net (code "157") (name "~{BH_R_RESET_3V}") (class "Default")
      (node (ref "P8") (pin "10") (pinfunction "10_10") (pintype "passive"))
      (node (ref "U2") (pin "5") (pinfunction "VIC_5") (pintype "input"))
    )
    (net (code "158") (name "~{BH_R_RESET}") (class "Default")
      (node (ref "BALL-HANDLE_RIGHT") (pin "4") (pinfunction "4_4") (pintype "passive"))
      (node (ref "U2") (pin "12") (pinfunction "VOC_12") (pintype "output"))
    )
  )
)
